# Power_Rail_Probe.net
KiCad netlist of a schematic drawn in Altium Designer
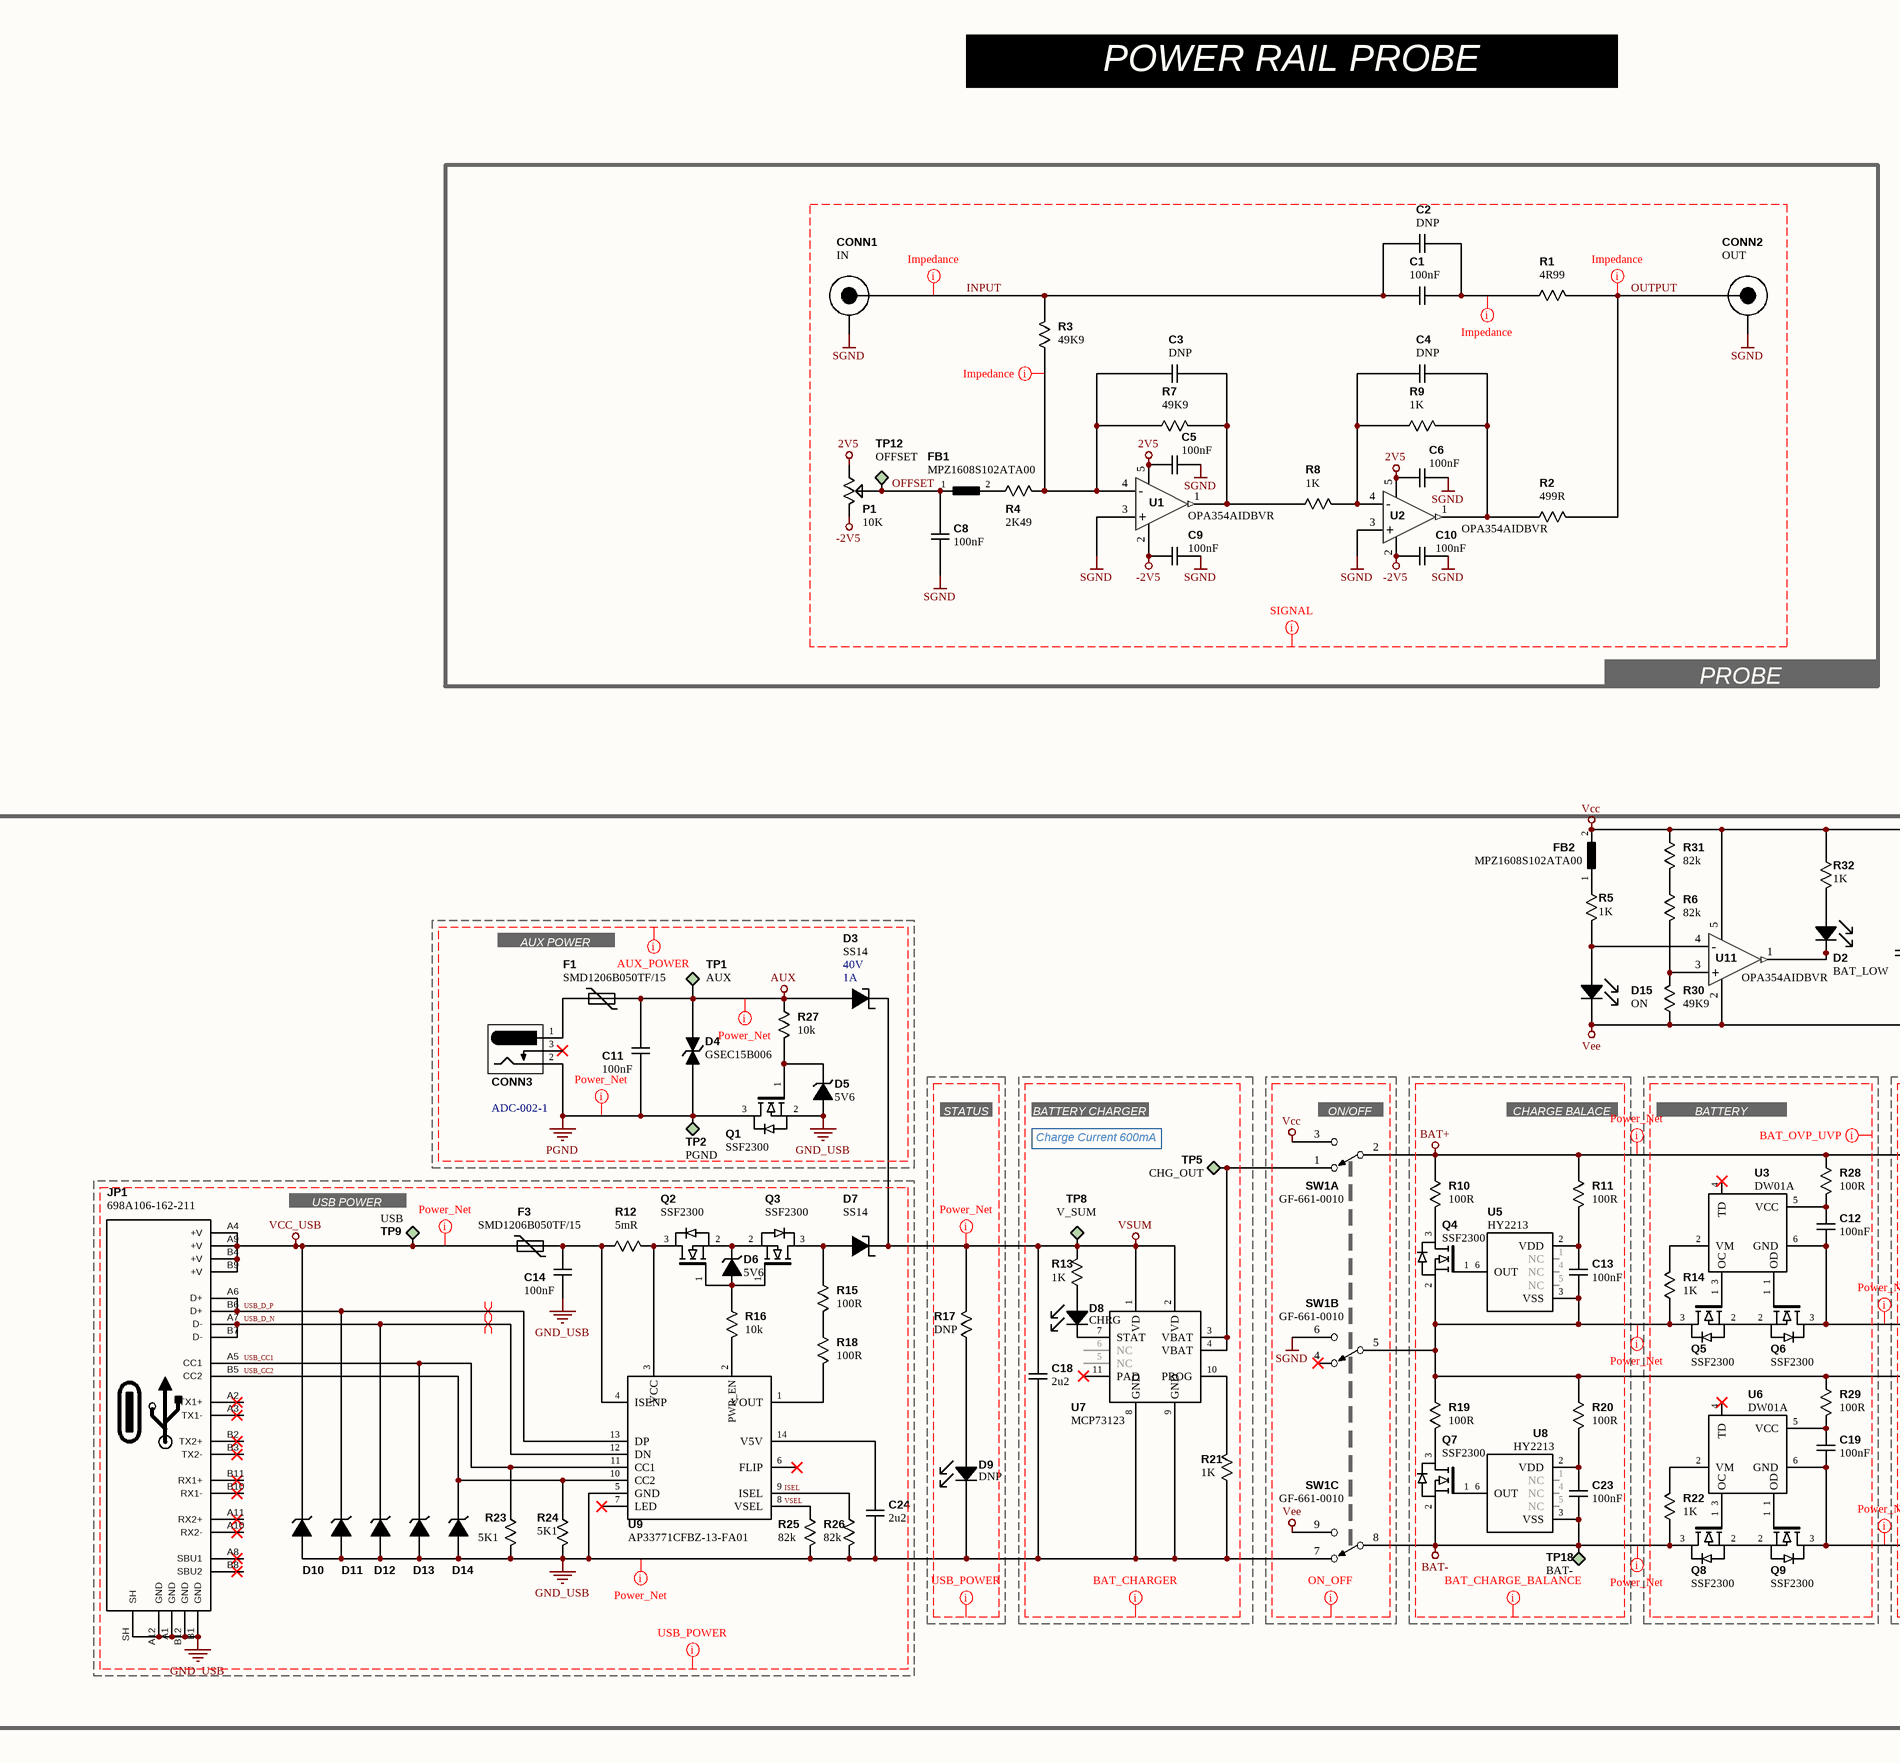
[diagram p0: Power_Rail_Probe.SchDoc, left]
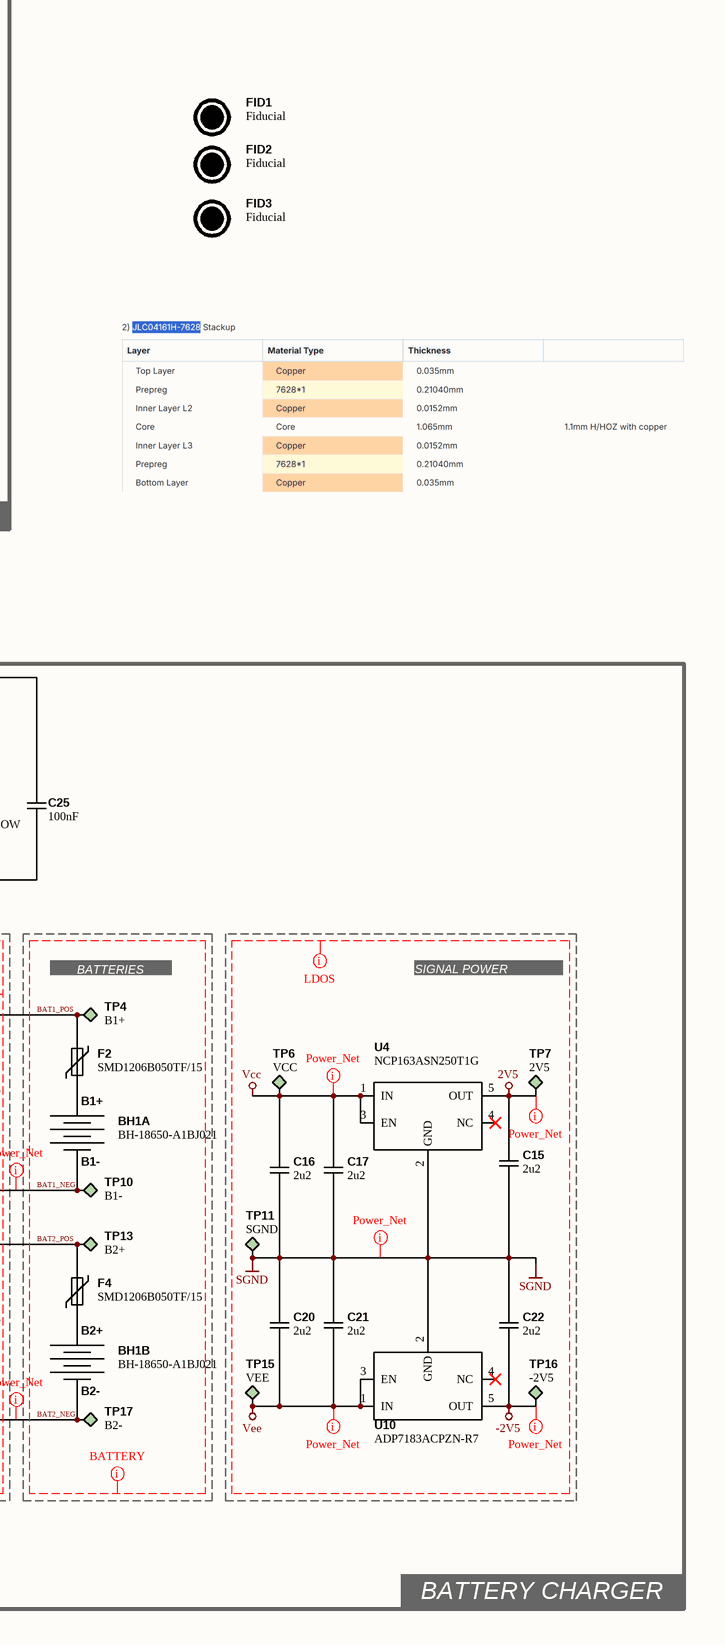
[diagram p1: Power_Rail_Probe.SchDoc, right]

(export (version "E")
  (design (tool "Eeschema 10.0.6"))
  (components
    (comp (ref "BH1")
      (value "BH-18650-A1BJ021")
      (footprint "BH-18650-A1BJ021")
      (description "2 Cell 18650 Battery Holder")
      (fields (field (name "05_DIGIKEY PART NUMBER") "Not Available"))
      (libsource (lib "Libreria_Altium") (part "BH-18650-A1BJ021"))
    )
    (comp (ref "C1")
      (value "100nF")
      (footprint "CAP_SMD_1206")
      (description "0.1 µF ±2% 50V Ceramic Capacitor C0G, NP0 1206 (3216 Metric)")
      (fields
        (field (name "04_MANUFACTURER PART NUMBER") "GRM3195C1H104GA05D")
        (field (name "05_DIGIKEY PART NUMBER") "490-GRM3195C1H104GA05DCT-ND")
      )
      (libsource (lib "Libreria_Altium") (part "Capacitor NP"))
    )
    (comp (ref "C2")
      (value "DNP")
      (footprint "CAP_SMD_0603")
      (description "0.1 µF ±10% 25V Ceramic Capacitor X7R 0603 (1608 Metric)")
      (fields
        (field (name "04_MANUFACTURER PART NUMBER") "CC0603KRX7R8BB104")
        (field (name "05_DIGIKEY PART NUMBER") "311-1341-1-ND")
      )
      (libsource (lib "Libreria_Altium") (part "Capacitor NP"))
    )
    (comp (ref "C3")
      (value "DNP")
      (footprint "CAP_SMD_0603")
      (description "0.1 µF ±10% 25V Ceramic Capacitor X7R 0603 (1608 Metric)")
      (fields
        (field (name "04_MANUFACTURER PART NUMBER") "CC0603KRX7R8BB104")
        (field (name "05_DIGIKEY PART NUMBER") "311-1341-1-ND")
      )
      (libsource (lib "Libreria_Altium") (part "Capacitor NP"))
    )
    (comp (ref "C4")
      (value "DNP")
      (footprint "CAP_SMD_0603")
      (description "0.1 µF ±10% 25V Ceramic Capacitor X7R 0603 (1608 Metric)")
      (fields
        (field (name "04_MANUFACTURER PART NUMBER") "CC0603KRX7R8BB104")
        (field (name "05_DIGIKEY PART NUMBER") "311-1341-1-ND")
      )
      (libsource (lib "Libreria_Altium") (part "Capacitor NP"))
    )
    (comp (ref "C5")
      (value "100nF")
      (footprint "CAP_SMD_0603")
      (description "0.1 µF ±10% 25V Ceramic Capacitor X7R 0603 (1608 Metric)")
      (fields
        (field (name "04_MANUFACTURER PART NUMBER") "CC0603KRX7R8BB104")
        (field (name "05_DIGIKEY PART NUMBER") "311-1341-1-ND")
      )
      (libsource (lib "Libreria_Altium") (part "Capacitor NP"))
    )
    (comp (ref "C6")
      (value "100nF")
      (footprint "CAP_SMD_0603")
      (description "0.1 µF ±10% 25V Ceramic Capacitor X7R 0603 (1608 Metric)")
      (fields
        (field (name "04_MANUFACTURER PART NUMBER") "CC0603KRX7R8BB104")
        (field (name "05_DIGIKEY PART NUMBER") "311-1341-1-ND")
      )
      (libsource (lib "Libreria_Altium") (part "Capacitor NP"))
    )
    (comp (ref "C8")
      (value "100nF")
      (footprint "CAP_SMD_0603")
      (description "0.1 µF ±10% 25V Ceramic Capacitor X7R 0603 (1608 Metric)")
      (fields
        (field (name "04_MANUFACTURER PART NUMBER") "CC0603KRX7R8BB104")
        (field (name "05_DIGIKEY PART NUMBER") "311-1341-1-ND")
      )
      (libsource (lib "Libreria_Altium") (part "Capacitor NP"))
    )
    (comp (ref "C9")
      (value "100nF")
      (footprint "CAP_SMD_0603")
      (description "0.1 µF ±10% 25V Ceramic Capacitor X7R 0603 (1608 Metric)")
      (fields
        (field (name "04_MANUFACTURER PART NUMBER") "CC0603KRX7R8BB104")
        (field (name "05_DIGIKEY PART NUMBER") "311-1341-1-ND")
      )
      (libsource (lib "Libreria_Altium") (part "Capacitor NP"))
    )
    (comp (ref "C10")
      (value "100nF")
      (footprint "CAP_SMD_0603")
      (description "0.1 µF ±10% 25V Ceramic Capacitor X7R 0603 (1608 Metric)")
      (fields
        (field (name "04_MANUFACTURER PART NUMBER") "CC0603KRX7R8BB104")
        (field (name "05_DIGIKEY PART NUMBER") "311-1341-1-ND")
      )
      (libsource (lib "Libreria_Altium") (part "Capacitor NP"))
    )
    (comp (ref "C11")
      (value "100nF")
      (footprint "CAP_SMD_0603")
      (description "0.1 µF ±10% 25V Ceramic Capacitor X7R 0603 (1608 Metric)")
      (fields
        (field (name "04_MANUFACTURER PART NUMBER") "CC0603KRX7R8BB104")
        (field (name "05_DIGIKEY PART NUMBER") "311-1341-1-ND")
      )
      (libsource (lib "Libreria_Altium") (part "Capacitor NP"))
    )
    (comp (ref "C12")
      (value "100nF")
      (footprint "CAP_SMD_0603")
      (description "0.1 µF ±10% 25V Ceramic Capacitor X7R 0603 (1608 Metric)")
      (fields
        (field (name "04_MANUFACTURER PART NUMBER") "CC0603KRX7R8BB104")
        (field (name "05_DIGIKEY PART NUMBER") "311-1341-1-ND")
      )
      (libsource (lib "Libreria_Altium") (part "Capacitor NP"))
    )
    (comp (ref "C13")
      (value "100nF")
      (footprint "CAP_SMD_0603")
      (description "0.1 µF ±10% 25V Ceramic Capacitor X7R 0603 (1608 Metric)")
      (fields
        (field (name "04_MANUFACTURER PART NUMBER") "CC0603KRX7R8BB104")
        (field (name "05_DIGIKEY PART NUMBER") "311-1341-1-ND")
      )
      (libsource (lib "Libreria_Altium") (part "Capacitor NP"))
    )
    (comp (ref "C14")
      (value "100nF")
      (footprint "CAP_SMD_0603")
      (description "0.1 µF ±10% 25V Ceramic Capacitor X7R 0603 (1608 Metric)")
      (fields
        (field (name "04_MANUFACTURER PART NUMBER") "CC0603KRX7R8BB104")
        (field (name "05_DIGIKEY PART NUMBER") "311-1341-1-ND")
      )
      (libsource (lib "Libreria_Altium") (part "Capacitor NP"))
    )
    (comp (ref "C15")
      (value "2u2")
      (footprint "CAP_SMD_0805")
      (description "2.2 µF ±10% 25V Ceramic Capacitor X7R 0805 (2012 Metric)")
      (fields
        (field (name "04_MANUFACTURER PART NUMBER") "GRM21BR71E225KE11K")
        (field (name "05_DIGIKEY PART NUMBER") "490-GRM21BR71E225KE11KCT-ND")
      )
      (libsource (lib "Libreria_Altium") (part "Capacitor NP"))
    )
    (comp (ref "C16")
      (value "2u2")
      (footprint "CAP_SMD_0805")
      (description "2.2 µF ±10% 25V Ceramic Capacitor X7R 0805 (2012 Metric)")
      (fields
        (field (name "04_MANUFACTURER PART NUMBER") "GRM21BR71E225KE11K")
        (field (name "05_DIGIKEY PART NUMBER") "490-GRM21BR71E225KE11KCT-ND")
      )
      (libsource (lib "Libreria_Altium") (part "Capacitor NP"))
    )
    (comp (ref "C17")
      (value "2u2")
      (footprint "CAP_SMD_0805")
      (description "2.2 µF ±10% 25V Ceramic Capacitor X7R 0805 (2012 Metric)")
      (fields
        (field (name "04_MANUFACTURER PART NUMBER") "GRM21BR71E225KE11K")
        (field (name "05_DIGIKEY PART NUMBER") "490-GRM21BR71E225KE11KCT-ND")
      )
      (libsource (lib "Libreria_Altium") (part "Capacitor NP"))
    )
    (comp (ref "C18")
      (value "2u2")
      (footprint "CAP_SMD_0805")
      (description "2.2 µF ±10% 25V Ceramic Capacitor X7R 0805 (2012 Metric)")
      (fields
        (field (name "04_MANUFACTURER PART NUMBER") "GRM21BR71E225KE11K")
        (field (name "05_DIGIKEY PART NUMBER") "490-GRM21BR71E225KE11KCT-ND")
      )
      (libsource (lib "Libreria_Altium") (part "Capacitor NP"))
    )
    (comp (ref "C19")
      (value "100nF")
      (footprint "CAP_SMD_0603")
      (description "0.1 µF ±10% 25V Ceramic Capacitor X7R 0603 (1608 Metric)")
      (fields
        (field (name "04_MANUFACTURER PART NUMBER") "CC0603KRX7R8BB104")
        (field (name "05_DIGIKEY PART NUMBER") "311-1341-1-ND")
      )
      (libsource (lib "Libreria_Altium") (part "Capacitor NP"))
    )
    (comp (ref "C20")
      (value "2u2")
      (footprint "CAP_SMD_0805")
      (description "2.2 µF ±10% 25V Ceramic Capacitor X7R 0805 (2012 Metric)")
      (fields
        (field (name "04_MANUFACTURER PART NUMBER") "GRM21BR71E225KE11K")
        (field (name "05_DIGIKEY PART NUMBER") "490-GRM21BR71E225KE11KCT-ND")
      )
      (libsource (lib "Libreria_Altium") (part "Capacitor NP"))
    )
    (comp (ref "C21")
      (value "2u2")
      (footprint "CAP_SMD_0805")
      (description "2.2 µF ±10% 25V Ceramic Capacitor X7R 0805 (2012 Metric)")
      (fields
        (field (name "04_MANUFACTURER PART NUMBER") "GRM21BR71E225KE11K")
        (field (name "05_DIGIKEY PART NUMBER") "490-GRM21BR71E225KE11KCT-ND")
      )
      (libsource (lib "Libreria_Altium") (part "Capacitor NP"))
    )
    (comp (ref "C22")
      (value "2u2")
      (footprint "CAP_SMD_0805")
      (description "2.2 µF ±10% 25V Ceramic Capacitor X7R 0805 (2012 Metric)")
      (fields
        (field (name "04_MANUFACTURER PART NUMBER") "GRM21BR71E225KE11K")
        (field (name "05_DIGIKEY PART NUMBER") "490-GRM21BR71E225KE11KCT-ND")
      )
      (libsource (lib "Libreria_Altium") (part "Capacitor NP"))
    )
    (comp (ref "C23")
      (value "100nF")
      (footprint "CAP_SMD_0603")
      (description "0.1 µF ±10% 25V Ceramic Capacitor X7R 0603 (1608 Metric)")
      (fields
        (field (name "04_MANUFACTURER PART NUMBER") "CC0603KRX7R8BB104")
        (field (name "05_DIGIKEY PART NUMBER") "311-1341-1-ND")
      )
      (libsource (lib "Libreria_Altium") (part "Capacitor NP"))
    )
    (comp (ref "C24")
      (value "2u2")
      (footprint "CAP_SMD_0805")
      (description "2.2 µF ±10% 25V Ceramic Capacitor X7R 0805 (2012 Metric)")
      (fields
        (field (name "04_MANUFACTURER PART NUMBER") "GRM21BR71E225KE11K")
        (field (name "05_DIGIKEY PART NUMBER") "490-GRM21BR71E225KE11KCT-ND")
      )
      (libsource (lib "Libreria_Altium") (part "Capacitor NP"))
    )
    (comp (ref "C25")
      (value "100nF")
      (footprint "CAP_SMD_0603")
      (description "0.1 µF ±10% 25V Ceramic Capacitor X7R 0603 (1608 Metric)")
      (fields
        (field (name "04_MANUFACTURER PART NUMBER") "CC0603KRX7R8BB104")
        (field (name "05_DIGIKEY PART NUMBER") "311-1341-1-ND")
      )
      (libsource (lib "Libreria_Altium") (part "Capacitor NP"))
    )
    (comp (ref "CONN1")
      (value "IN")
      (footprint "CONBNC002")
      (description "BNC Connector Jack, Female Socket 50 Ohms Panel Mount, Through Hole, Right Angle Solder")
      (fields
        (field (name "04_MANUFACTURER PART NUMBER") "CONBNC002")
        (field (name "05_DIGIKEY PART NUMBER") "343-CONBNC002-ND")
      )
      (libsource (lib "Libreria_Altium") (part "Conector BNC"))
    )
    (comp (ref "CONN2")
      (value "OUT")
      (footprint "CONBNC002")
      (description "BNC Connector Jack, Female Socket 50 Ohms Panel Mount, Through Hole, Right Angle Solder")
      (fields
        (field (name "04_MANUFACTURER PART NUMBER") "CONBNC002")
        (field (name "05_DIGIKEY PART NUMBER") "343-CONBNC002-ND")
      )
      (libsource (lib "Libreria_Altium") (part "Conector BNC"))
    )
    (comp (ref "CONN3")
      (value "AUX")
      (footprint "ADC-002A")
      (description "DC JACK")
      (fields
        (field (name "04_MANUFACTURER PART NUMBER") "ADC-002-1")
        (field (name "05_DIGIKEY PART NUMBER") "2057-ADC-002-1-ND")
      )
      (libsource (lib "Libreria_Altium") (part "DC JACK"))
    )
    (comp (ref "D2")
      (value "BAT_LOW")
      (footprint "LED_0603_1608")
      (description "Diodo LEd")
      (fields
        (field (name "04_MANUFACTURER PART NUMBER") "SML-D12U1WT86")
        (field (name "05_DIGIKEY PART NUMBER") "SML-D12U1WT86CT-ND")
      )
      (libsource (lib "Libreria_Altium") (part "Diodo LED"))
    )
    (comp (ref "D3")
      (value "SS14")
      (footprint "DO_214_AC")
      (description "Diode 40 V 1A Surface Mount DO-214AC (SMA)")
      (fields
        (field (name "04_MANUFACTURER PART NUMBER") "SS14-M3/5AT")
        (field (name "05_DIGIKEY PART NUMBER") "SS14-M3/5ATGICT-ND")
        (field (name "07_TENSIÓN") "40V")
        (field (name "08_CORRIENTE") "1A")
      )
      (libsource (lib "Libreria_Altium") (part "Diodo Schottky"))
    )
    (comp (ref "D4")
      (value "GSEC15B006")
      (footprint "SOD_323")
      (description "Diodo TVS")
      (fields (field (name "05_DIGIKEY PART NUMBER") "4786-GSEC15B006CT-ND"))
      (libsource (lib "Libreria_Altium") (part "Diodo TVS Bidireccional"))
    )
    (comp (ref "D5")
      (value "5V6")
      (footprint "SOD_323")
      (description "Diodo Zener")
      (fields
        (field (name "04_MANUFACTURER PART NUMBER") "BZT52C5V6S-7-F")
        (field (name "05_DIGIKEY PART NUMBER") "BZT52C5V6S-FDICT-ND")
      )
      (libsource (lib "Libreria_Altium") (part "Diodo Zener"))
    )
    (comp (ref "D6")
      (value "5V6")
      (footprint "SOD_323")
      (description "Diodo Zener")
      (fields
        (field (name "04_MANUFACTURER PART NUMBER") "BZT52C5V6S-7-F")
        (field (name "05_DIGIKEY PART NUMBER") "BZT52C5V6S-FDICT-ND")
      )
      (libsource (lib "Libreria_Altium") (part "Diodo Zener"))
    )
    (comp (ref "D7")
      (value "SS14")
      (footprint "DO_214_AC")
      (description "Diode 40 V 1A Surface Mount DO-214AC (SMA)")
      (fields
        (field (name "04_MANUFACTURER PART NUMBER") "SS14-M3/5AT")
        (field (name "05_DIGIKEY PART NUMBER") "SS14-M3/5ATGICT-ND")
      )
      (libsource (lib "Libreria_Altium") (part "Diodo Schottky"))
    )
    (comp (ref "D8")
      (value "CHRG")
      (footprint "LED_0603_1608")
      (description "Diodo LEd")
      (fields
        (field (name "04_MANUFACTURER PART NUMBER") "SML-D12U1WT86")
        (field (name "05_DIGIKEY PART NUMBER") "SML-D12U1WT86CT-ND")
      )
      (libsource (lib "Libreria_Altium") (part "Diodo LED"))
    )
    (comp (ref "D9")
      (value "DNP")
      (footprint "LED_0603_1608")
      (description "Diodo LEd")
      (fields
        (field (name "04_MANUFACTURER PART NUMBER") "SML-D12U1WT86")
        (field (name "05_DIGIKEY PART NUMBER") "SML-D12U1WT86CT-ND")
      )
      (libsource (lib "Libreria_Altium") (part "Diodo LED"))
    )
    (comp (ref "D10")
      (value "GSEC15B006")
      (footprint "SOD_323")
      (description "Diodo TVS")
      (fields (field (name "05_DIGIKEY PART NUMBER") "4786-GSEC15B006CT-ND"))
      (libsource (lib "Libreria_Altium") (part "Diodo TVS Unidireccional"))
    )
    (comp (ref "D11")
      (value "GSEC15B006")
      (footprint "SOD_323")
      (description "Diodo TVS")
      (fields (field (name "05_DIGIKEY PART NUMBER") "4786-GSEC15B006CT-ND"))
      (libsource (lib "Libreria_Altium") (part "Diodo TVS Unidireccional"))
    )
    (comp (ref "D12")
      (value "GSEC15B006")
      (footprint "SOD_323")
      (description "Diodo TVS")
      (fields (field (name "05_DIGIKEY PART NUMBER") "4786-GSEC15B006CT-ND"))
      (libsource (lib "Libreria_Altium") (part "Diodo TVS Unidireccional"))
    )
    (comp (ref "D13")
      (value "GSEC15B006")
      (footprint "SOD_323")
      (description "Diodo TVS")
      (fields (field (name "05_DIGIKEY PART NUMBER") "4786-GSEC15B006CT-ND"))
      (libsource (lib "Libreria_Altium") (part "Diodo TVS Unidireccional"))
    )
    (comp (ref "D14")
      (value "GSEC15B006")
      (footprint "SOD_323")
      (description "Diodo TVS")
      (fields (field (name "05_DIGIKEY PART NUMBER") "4786-GSEC15B006CT-ND"))
      (libsource (lib "Libreria_Altium") (part "Diodo TVS Unidireccional"))
    )
    (comp (ref "D15")
      (value "ON")
      (footprint "LED_0603_1608")
      (description "Diodo LEd")
      (fields
        (field (name "04_MANUFACTURER PART NUMBER") "SML-D12U1WT86")
        (field (name "05_DIGIKEY PART NUMBER") "SML-D12U1WT86CT-ND")
      )
      (libsource (lib "Libreria_Altium") (part "Diodo LED"))
    )
    (comp (ref "F1")
      (value "SMD1206B050TF/15")
      (footprint "RES_SMD_1210")
      (description "Polymeric PTC Resettable Fuse 15V 500 mA Ih Surface Mount 1206 (3216 Metric), Concave")
      (fields (field (name "05_DIGIKEY PART NUMBER") "13-SMD1206B050TF/15CT-ND"))
      (libsource (lib "") (part "Polyswitch_1"))
    )
    (comp (ref "F2")
      (value "SMD1206B050TF/15")
      (footprint "RES_SMD_1210")
      (description "Polymeric PTC Resettable Fuse 15V 500 mA Ih Surface Mount 1206 (3216 Metric), Concave")
      (fields (field (name "05_DIGIKEY PART NUMBER") "13-SMD1206B050TF/15CT-ND"))
      (libsource (lib "Libreria_Altium") (part "Polyswitch"))
    )
    (comp (ref "F3")
      (value "SMD1206B050TF/15")
      (footprint "RES_SMD_1210")
      (description "Polymeric PTC Resettable Fuse 15V 500 mA Ih Surface Mount 1206 (3216 Metric), Concave")
      (fields (field (name "05_DIGIKEY PART NUMBER") "13-SMD1206B050TF/15CT-ND"))
      (libsource (lib "") (part "Polyswitch_1"))
    )
    (comp (ref "F4")
      (value "SMD1206B050TF/15")
      (footprint "RES_SMD_1210")
      (description "Polymeric PTC Resettable Fuse 15V 500 mA Ih Surface Mount 1206 (3216 Metric), Concave")
      (fields (field (name "05_DIGIKEY PART NUMBER") "13-SMD1206B050TF/15CT-ND"))
      (libsource (lib "Libreria_Altium") (part "Polyswitch"))
    )
    (comp (ref "FB1")
      (value "MPZ1608S102ATA00")
      (footprint "FERRITE_SMD_0603")
      (description "1 kOhms @ 100 MHz 1 Power Line Ferrite Bead 0603 (1608 Metric) 800mA 300mOhm")
      (fields (field (name "05_DIGIKEY PART NUMBER") "445-MPZ1608S102ATA00CT-ND"))
      (libsource (lib "Libreria_Altium") (part "Ferrite Bead"))
    )
    (comp (ref "FB2")
      (value "MPZ1608S102ATA00")
      (footprint "FERRITE_SMD_0603")
      (description "1 kOhms @ 100 MHz 1 Power Line Ferrite Bead 0603 (1608 Metric) 800mA 300mOhm")
      (fields (field (name "05_DIGIKEY PART NUMBER") "445-MPZ1608S102ATA00CT-ND"))
      (libsource (lib "") (part "Ferrite Bead_1"))
    )
    (comp (ref "FID1")
      (value "Fiducial")
      (footprint "Fiducial")
      (description "Fiducial SMD")
      (libsource (lib "Libreria_Altium") (part "Fiducial"))
    )
    (comp (ref "FID2")
      (value "Fiducial")
      (footprint "Fiducial")
      (description "Fiducial SMD")
      (libsource (lib "Libreria_Altium") (part "Fiducial"))
    )
    (comp (ref "FID3")
      (value "Fiducial")
      (footprint "Fiducial")
      (description "Fiducial SMD")
      (libsource (lib "Libreria_Altium") (part "Fiducial"))
    )
    (comp (ref "JP1")
      (value "698A106-162-211")
      (footprint "1054500101")
      (fields
        (field (name "04_MANUFACTURER PART NUMBER") "1054500101")
        (field (name "05_DIGIKEY PART NUMBER") "WM12856CT-ND")
      )
      (libsource (lib "Libreria_Altium") (part "USB C 3.0"))
    )
    (comp (ref "P1")
      (value "10K")
      (footprint "POTENCIOMETRO_RK09K1110A0J")
      (description "10k Ohm 1 Gang Linear Through Hole Potentiometer 1.0 Turns Carbon 0.05W, 1/20W PC Pins")
      (fields
        (field (name "04_MANUFACTURER PART NUMBER") "RK09K1110A0J")
        (field (name "05_DIGIKEY PART NUMBER") "4809-RK09K1110A0J-ND")
      )
      (libsource (lib "Libreria_Altium") (part "POTENCIÓMETRO"))
    )
    (comp (ref "Q1")
      (value "SSF2300")
      (footprint "SOT_23-3")
      (description "N-Channel MOSFET SOT-23")
      (fields
        (field (name "04_MANUFACTURER PART NUMBER") "AO3414A")
        (field (name "05_DIGIKEY PART NUMBER") "4518-AO3414ACT-ND")
      )
      (libsource (lib "") (part "NMOS_1"))
    )
    (comp (ref "Q2")
      (value "SSF2300")
      (footprint "SOT_23-3")
      (description "N-Channel MOSFET SOT-23")
      (fields
        (field (name "04_MANUFACTURER PART NUMBER") "AO3414A")
        (field (name "05_DIGIKEY PART NUMBER") "4518-AO3414ACT-ND")
      )
      (libsource (lib "") (part "NMOS_2"))
    )
    (comp (ref "Q3")
      (value "SSF2300")
      (footprint "SOT_23-3")
      (description "N-Channel MOSFET SOT-23")
      (fields
        (field (name "04_MANUFACTURER PART NUMBER") "AO3414A")
        (field (name "05_DIGIKEY PART NUMBER") "4518-AO3414ACT-ND")
      )
      (libsource (lib "") (part "NMOS_3"))
    )
    (comp (ref "Q4")
      (value "SSF2300")
      (footprint "SOT_23-3")
      (description "N-Channel MOSFET SOT-23")
      (fields
        (field (name "04_MANUFACTURER PART NUMBER") "AO3414A")
        (field (name "05_DIGIKEY PART NUMBER") "4518-AO3414ACT-ND")
      )
      (libsource (lib "Libreria_Altium") (part "NMOS"))
    )
    (comp (ref "Q5")
      (value "SSF2300")
      (footprint "SOT_23-3")
      (description "N-Channel MOSFET SOT-23")
      (fields
        (field (name "04_MANUFACTURER PART NUMBER") "AO3414A")
        (field (name "05_DIGIKEY PART NUMBER") "4518-AO3414ACT-ND")
      )
      (libsource (lib "") (part "NMOS_1"))
    )
    (comp (ref "Q6")
      (value "SSF2300")
      (footprint "SOT_23-3")
      (description "N-Channel MOSFET SOT-23")
      (fields
        (field (name "04_MANUFACTURER PART NUMBER") "AO3414A")
        (field (name "05_DIGIKEY PART NUMBER") "4518-AO3414ACT-ND")
      )
      (libsource (lib "Libreria_Altium") (part "NMOS"))
    )
    (comp (ref "Q7")
      (value "SSF2300")
      (footprint "SOT_23-3")
      (description "N-Channel MOSFET SOT-23")
      (fields
        (field (name "04_MANUFACTURER PART NUMBER") "AO3414A")
        (field (name "05_DIGIKEY PART NUMBER") "4518-AO3414ACT-ND")
      )
      (libsource (lib "Libreria_Altium") (part "NMOS"))
    )
    (comp (ref "Q8")
      (value "SSF2300")
      (footprint "SOT_23-3")
      (description "N-Channel MOSFET SOT-23")
      (fields
        (field (name "04_MANUFACTURER PART NUMBER") "AO3414A")
        (field (name "05_DIGIKEY PART NUMBER") "4518-AO3414ACT-ND")
      )
      (libsource (lib "") (part "NMOS_1"))
    )
    (comp (ref "Q9")
      (value "SSF2300")
      (footprint "SOT_23-3")
      (description "N-Channel MOSFET SOT-23")
      (fields
        (field (name "04_MANUFACTURER PART NUMBER") "AO3414A")
        (field (name "05_DIGIKEY PART NUMBER") "4518-AO3414ACT-ND")
      )
      (libsource (lib "Libreria_Altium") (part "NMOS"))
    )
    (comp (ref "R1")
      (value "4R99")
      (footprint "RES_SMD_0603")
      (description "4.99 Ohms ±0.1% 0.1W, 1/10W Chip Resistor 0603 (1608 Metric) Thin Film")
      (fields
        (field (name "04_MANUFACTURER PART NUMBER") "RT0603BRD074R99L")
        (field (name "05_DIGIKEY PART NUMBER") "13-RT0603BRD074R99LCT-ND")
      )
      (libsource (lib "Libreria_Altium") (part "Resistor"))
    )
    (comp (ref "R2")
      (value "499R")
      (footprint "RES_SMD_0603")
      (description "499 Ohms ±0.1% 0.167W, 1/6W Chip Resistor 0603 (1608 Metric) Automotive AEC-Q200 Thin Film")
      (fields
        (field (name "04_MANUFACTURER PART NUMBER") "RNCF0603BTE499R")
        (field (name "05_DIGIKEY PART NUMBER") "738-RNCF0603BTE499RCT-ND")
      )
      (libsource (lib "Libreria_Altium") (part "Resistor"))
    )
    (comp (ref "R3")
      (value "49K9")
      (footprint "RES_SMD_0603")
      (description "49.9 kOhms ±0.1% 0.167W, 1/6W Chip Resistor 0603 (1608 Metric) Automotive AEC-Q200 Thin Film")
      (fields
        (field (name "04_MANUFACTURER PART NUMBER") "RNCF0603BTE49K9")
        (field (name "05_DIGIKEY PART NUMBER") "738-RNCF0603BTE49K9CT-ND")
      )
      (libsource (lib "Libreria_Altium") (part "Resistor"))
    )
    (comp (ref "R4")
      (value "2K49")
      (footprint "RES_SMD_0603")
      (description "2.49 kOhms ±0.1% 0.167W, 1/6W Chip Resistor 0603 (1608 Metric) Automotive AEC-Q200 Thin Film")
      (fields
        (field (name "04_MANUFACTURER PART NUMBER") "RNCF0603BKE2K49")
        (field (name "05_DIGIKEY PART NUMBER") "738-RNCF0603BKE2K49CT-ND")
      )
      (libsource (lib "Libreria_Altium") (part "Resistor"))
    )
    (comp (ref "R5")
      (value "1K")
      (footprint "RES_SMD_0603")
      (description "1 kOhms ±0.1% 0.167W, 1/6W Chip Resistor 0603 (1608 Metric) Automotive AEC-Q200 Thin Film")
      (fields
        (field (name "04_MANUFACTURER PART NUMBER") "RNCF0603BTE1K00")
        (field (name "05_DIGIKEY PART NUMBER") "738-RNCF0603BTE1K00CT-ND")
      )
      (libsource (lib "Libreria_Altium") (part "Resistor"))
    )
    (comp (ref "R6")
      (value "82k")
      (footprint "RES_SMD_0603")
      (description "82 kOhms ±1% 0.1W, 1/10W Chip Resistor 0603 (1608 Metric) Automotive AEC-Q200 Thick Film")
      (fields
        (field (name "04_MANUFACTURER PART NUMBER") "RMCF0603FT82K0")
        (field (name "05_DIGIKEY PART NUMBER") "RMCF0603FT82K0CT-ND")
      )
      (libsource (lib "Libreria_Altium") (part "Resistor"))
    )
    (comp (ref "R7")
      (value "49K9")
      (footprint "RES_SMD_0603")
      (description "49.9 kOhms ±0.1% 0.167W, 1/6W Chip Resistor 0603 (1608 Metric) Automotive AEC-Q200 Thin Film")
      (fields
        (field (name "04_MANUFACTURER PART NUMBER") "RNCF0603BTE49K9")
        (field (name "05_DIGIKEY PART NUMBER") "738-RNCF0603BTE49K9CT-ND")
      )
      (libsource (lib "Libreria_Altium") (part "Resistor"))
    )
    (comp (ref "R8")
      (value "1K")
      (footprint "RES_SMD_0603")
      (description "1 kOhms ±0.1% 0.167W, 1/6W Chip Resistor 0603 (1608 Metric) Automotive AEC-Q200 Thin Film")
      (fields
        (field (name "04_MANUFACTURER PART NUMBER") "RNCF0603BTE1K00")
        (field (name "05_DIGIKEY PART NUMBER") "738-RNCF0603BTE1K00CT-ND")
      )
      (libsource (lib "Libreria_Altium") (part "Resistor"))
    )
    (comp (ref "R9")
      (value "1K")
      (footprint "RES_SMD_0603")
      (description "1 kOhms ±0.1% 0.167W, 1/6W Chip Resistor 0603 (1608 Metric) Automotive AEC-Q200 Thin Film")
      (fields
        (field (name "04_MANUFACTURER PART NUMBER") "RNCF0603BTE1K00")
        (field (name "05_DIGIKEY PART NUMBER") "738-RNCF0603BTE1K00CT-ND")
      )
      (libsource (lib "Libreria_Altium") (part "Resistor"))
    )
    (comp (ref "R10")
      (value "100R")
      (footprint "RES_SMD_0603")
      (fields
        (field (name "04_MANUFACTURER PART NUMBER") "RMCF0603FT100R")
        (field (name "05_DIGIKEY PART NUMBER") "RMCF0603FT100RCT-ND")
      )
      (libsource (lib "Libreria_Altium") (part "Resistor"))
    )
    (comp (ref "R11")
      (value "100R")
      (footprint "RES_SMD_0603")
      (fields
        (field (name "04_MANUFACTURER PART NUMBER") "RMCF0603FT100R")
        (field (name "05_DIGIKEY PART NUMBER") "RMCF0603FT100RCT-ND")
      )
      (libsource (lib "Libreria_Altium") (part "Resistor"))
    )
    (comp (ref "R12")
      (value "5mR")
      (footprint "RES_SMD_0805")
      (description "5 mOhms ±1% 0.125W, 1/8W Chip Resistor 0805 (2012 Metric) Current Sense Metal Foil")
      (fields
        (field (name "04_MANUFACTURER PART NUMBER") "PE0805FRM070R005Z")
        (field (name "05_DIGIKEY PART NUMBER") "13-PE0805FRM070R005ZCT-ND")
      )
      (libsource (lib "Libreria_Altium") (part "Resistor"))
    )
    (comp (ref "R13")
      (value "1K")
      (footprint "RES_SMD_0603")
      (description "1 kOhms ±0.1% 0.167W, 1/6W Chip Resistor 0603 (1608 Metric) Automotive AEC-Q200 Thin Film")
      (fields
        (field (name "04_MANUFACTURER PART NUMBER") "RNCF0603BTE1K00")
        (field (name "05_DIGIKEY PART NUMBER") "738-RNCF0603BTE1K00CT-ND")
      )
      (libsource (lib "Libreria_Altium") (part "Resistor"))
    )
    (comp (ref "R14")
      (value "1K")
      (footprint "RES_SMD_0603")
      (description "1 kOhms ±0.1% 0.167W, 1/6W Chip Resistor 0603 (1608 Metric) Automotive AEC-Q200 Thin Film")
      (fields
        (field (name "04_MANUFACTURER PART NUMBER") "RNCF0603BTE1K00")
        (field (name "05_DIGIKEY PART NUMBER") "738-RNCF0603BTE1K00CT-ND")
      )
      (libsource (lib "Libreria_Altium") (part "Resistor"))
    )
    (comp (ref "R15")
      (value "100R")
      (footprint "RES_SMD_0603")
      (fields
        (field (name "04_MANUFACTURER PART NUMBER") "RMCF0603FT100R")
        (field (name "05_DIGIKEY PART NUMBER") "RMCF0603FT100RCT-ND")
      )
      (libsource (lib "Libreria_Altium") (part "Resistor"))
    )
    (comp (ref "R16")
      (value "10k")
      (footprint "RES_SMD_0603")
      (description "10 kOhms ±1% 0.1W, 1/10W Chip Resistor 0603 (1608 Metric) Automotive AEC-Q200 Thick Film")
      (fields
        (field (name "04_MANUFACTURER PART NUMBER") "RMCF0603FT10K0")
        (field (name "05_DIGIKEY PART NUMBER") "RMCF0603FT10K0CT-ND")
      )
      (libsource (lib "Libreria_Altium") (part "Resistor"))
    )
    (comp (ref "R17")
      (value "DNP")
      (footprint "RES_SMD_0603")
      (description "1 kOhms ±0.1% 0.167W, 1/6W Chip Resistor 0603 (1608 Metric) Automotive AEC-Q200 Thin Film")
      (fields
        (field (name "04_MANUFACTURER PART NUMBER") "RNCF0603BTE1K00")
        (field (name "05_DIGIKEY PART NUMBER") "738-RNCF0603BTE1K00CT-ND")
      )
      (libsource (lib "Libreria_Altium") (part "Resistor"))
    )
    (comp (ref "R18")
      (value "100R")
      (footprint "RES_SMD_0603")
      (fields
        (field (name "04_MANUFACTURER PART NUMBER") "RMCF0603FT100R")
        (field (name "05_DIGIKEY PART NUMBER") "RMCF0603FT100RCT-ND")
      )
      (libsource (lib "Libreria_Altium") (part "Resistor"))
    )
    (comp (ref "R19")
      (value "100R")
      (footprint "RES_SMD_0603")
      (fields
        (field (name "04_MANUFACTURER PART NUMBER") "RMCF0603FT100R")
        (field (name "05_DIGIKEY PART NUMBER") "RMCF0603FT100RCT-ND")
      )
      (libsource (lib "Libreria_Altium") (part "Resistor"))
    )
    (comp (ref "R20")
      (value "100R")
      (footprint "RES_SMD_0603")
      (fields
        (field (name "04_MANUFACTURER PART NUMBER") "RMCF0603FT100R")
        (field (name "05_DIGIKEY PART NUMBER") "RMCF0603FT100RCT-ND")
      )
      (libsource (lib "Libreria_Altium") (part "Resistor"))
    )
    (comp (ref "R21")
      (value "1K")
      (footprint "RES_SMD_0603")
      (description "1 kOhms ±0.1% 0.167W, 1/6W Chip Resistor 0603 (1608 Metric) Automotive AEC-Q200 Thin Film")
      (fields
        (field (name "04_MANUFACTURER PART NUMBER") "RNCF0603BTE1K00")
        (field (name "05_DIGIKEY PART NUMBER") "738-RNCF0603BTE1K00CT-ND")
      )
      (libsource (lib "Libreria_Altium") (part "Resistor"))
    )
    (comp (ref "R22")
      (value "1K")
      (footprint "RES_SMD_0603")
      (description "1 kOhms ±0.1% 0.167W, 1/6W Chip Resistor 0603 (1608 Metric) Automotive AEC-Q200 Thin Film")
      (fields
        (field (name "04_MANUFACTURER PART NUMBER") "RNCF0603BTE1K00")
        (field (name "05_DIGIKEY PART NUMBER") "738-RNCF0603BTE1K00CT-ND")
      )
      (libsource (lib "Libreria_Altium") (part "Resistor"))
    )
    (comp (ref "R23")
      (value "5K1")
      (footprint "RES_SMD_0603")
      (description "5.1 kOhms ±1% 0.1W, 1/10W Chip Resistor 0603 (1608 Metric) Automotive AEC-Q200 Thick Film")
      (fields
        (field (name "04_MANUFACTURER PART NUMBER") "RMCF0603FT5K10")
        (field (name "05_DIGIKEY PART NUMBER") "RMCF0603FT5K10CT-ND")
      )
      (libsource (lib "Libreria_Altium") (part "Resistor"))
    )
    (comp (ref "R24")
      (value "5K1")
      (footprint "RES_SMD_0603")
      (description "5.1 kOhms ±1% 0.1W, 1/10W Chip Resistor 0603 (1608 Metric) Automotive AEC-Q200 Thick Film")
      (fields
        (field (name "04_MANUFACTURER PART NUMBER") "RMCF0603FT5K10")
        (field (name "05_DIGIKEY PART NUMBER") "RMCF0603FT5K10CT-ND")
      )
      (libsource (lib "Libreria_Altium") (part "Resistor"))
    )
    (comp (ref "R25")
      (value "82k")
      (footprint "RES_SMD_0603")
      (description "82 kOhms ±1% 0.1W, 1/10W Chip Resistor 0603 (1608 Metric) Automotive AEC-Q200 Thick Film")
      (fields
        (field (name "04_MANUFACTURER PART NUMBER") "RMCF0603FT82K0")
        (field (name "05_DIGIKEY PART NUMBER") "RMCF0603FT82K0CT-ND")
      )
      (libsource (lib "Libreria_Altium") (part "Resistor"))
    )
    (comp (ref "R26")
      (value "82k")
      (footprint "RES_SMD_0603")
      (description "82 kOhms ±1% 0.1W, 1/10W Chip Resistor 0603 (1608 Metric) Automotive AEC-Q200 Thick Film")
      (fields
        (field (name "04_MANUFACTURER PART NUMBER") "RMCF0603FT82K0")
        (field (name "05_DIGIKEY PART NUMBER") "RMCF0603FT82K0CT-ND")
      )
      (libsource (lib "Libreria_Altium") (part "Resistor"))
    )
    (comp (ref "R27")
      (value "10k")
      (footprint "RES_SMD_0603")
      (description "10 kOhms ±1% 0.1W, 1/10W Chip Resistor 0603 (1608 Metric) Automotive AEC-Q200 Thick Film")
      (fields
        (field (name "04_MANUFACTURER PART NUMBER") "RMCF0603FT10K0")
        (field (name "05_DIGIKEY PART NUMBER") "RMCF0603FT10K0CT-ND")
      )
      (libsource (lib "Libreria_Altium") (part "Resistor"))
    )
    (comp (ref "R28")
      (value "100R")
      (footprint "RES_SMD_0603")
      (fields
        (field (name "04_MANUFACTURER PART NUMBER") "RMCF0603FT100R")
        (field (name "05_DIGIKEY PART NUMBER") "RMCF0603FT100RCT-ND")
      )
      (libsource (lib "Libreria_Altium") (part "Resistor"))
    )
    (comp (ref "R29")
      (value "100R")
      (footprint "RES_SMD_0603")
      (fields
        (field (name "04_MANUFACTURER PART NUMBER") "RMCF0603FT100R")
        (field (name "05_DIGIKEY PART NUMBER") "RMCF0603FT100RCT-ND")
      )
      (libsource (lib "Libreria_Altium") (part "Resistor"))
    )
    (comp (ref "R30")
      (value "49K9")
      (footprint "RES_SMD_0603")
      (description "49.9 kOhms ±0.1% 0.167W, 1/6W Chip Resistor 0603 (1608 Metric) Automotive AEC-Q200 Thin Film")
      (fields
        (field (name "04_MANUFACTURER PART NUMBER") "RNCF0603BTE49K9")
        (field (name "05_DIGIKEY PART NUMBER") "738-RNCF0603BTE49K9CT-ND")
      )
      (libsource (lib "Libreria_Altium") (part "Resistor"))
    )
    (comp (ref "R31")
      (value "82k")
      (footprint "RES_SMD_0603")
      (description "82 kOhms ±1% 0.1W, 1/10W Chip Resistor 0603 (1608 Metric) Automotive AEC-Q200 Thick Film")
      (fields
        (field (name "04_MANUFACTURER PART NUMBER") "RMCF0603FT82K0")
        (field (name "05_DIGIKEY PART NUMBER") "RMCF0603FT82K0CT-ND")
      )
      (libsource (lib "Libreria_Altium") (part "Resistor"))
    )
    (comp (ref "R32")
      (value "1K")
      (footprint "RES_SMD_0603")
      (description "1 kOhms ±0.1% 0.167W, 1/6W Chip Resistor 0603 (1608 Metric) Automotive AEC-Q200 Thin Film")
      (fields
        (field (name "04_MANUFACTURER PART NUMBER") "RNCF0603BTE1K00")
        (field (name "05_DIGIKEY PART NUMBER") "738-RNCF0603BTE1K00CT-ND")
      )
      (libsource (lib "Libreria_Altium") (part "Resistor"))
    )
    (comp (ref "SW1")
      (value "GF-661-0010")
      (footprint "1003P1T2B1M2QEH")
      (description "Slide Switch 3PDT Through Hole")
      (fields
        (field (name "04_MANUFACTURER PART NUMBER") "1003P1T1B1M2QEH")
        (field (name "05_DIGIKEY PART NUMBER") "EG2425-ND")
      )
      (libsource (lib "Libreria_Altium") (part "Interruptor 3PDT"))
    )
    (comp (ref "TP1")
      (value "AUX")
      (footprint "Test_Point_THT")
      (description "Testpoint")
      (fields (field (name "04_MANUFACTURER PART NUMBER") "NA"))
      (libsource (lib "Libreria_Altium") (part "TestPoint_SMD"))
    )
    (comp (ref "TP2")
      (value "PGND")
      (footprint "Test_Point_THT")
      (description "Testpoint")
      (fields (field (name "04_MANUFACTURER PART NUMBER") "NA"))
      (libsource (lib "Libreria_Altium") (part "TestPoint_SMD"))
    )
    (comp (ref "TP4")
      (value "B1+")
      (footprint "Test_Point_SMD")
      (description "Testpoint")
      (fields (field (name "04_MANUFACTURER PART NUMBER") "NA"))
      (libsource (lib "Libreria_Altium") (part "TestPoint_SMD"))
    )
    (comp (ref "TP5")
      (value "CHG_OUT")
      (footprint "Test_Point_THT")
      (description "Testpoint")
      (fields (field (name "04_MANUFACTURER PART NUMBER") "NA"))
      (libsource (lib "Libreria_Altium") (part "TestPoint_SMD"))
    )
    (comp (ref "TP6")
      (value "VCC")
      (footprint "Test_Point_THT")
      (description "Testpoint")
      (fields (field (name "04_MANUFACTURER PART NUMBER") "NA"))
      (libsource (lib "Libreria_Altium") (part "TestPoint_SMD"))
    )
    (comp (ref "TP7")
      (value "2V5")
      (footprint "Test_Point_THT")
      (description "Testpoint")
      (fields (field (name "04_MANUFACTURER PART NUMBER") "NA"))
      (libsource (lib "Libreria_Altium") (part "TestPoint_SMD"))
    )
    (comp (ref "TP8")
      (value "V_SUM")
      (footprint "Test_Point_THT")
      (description "Testpoint")
      (fields (field (name "04_MANUFACTURER PART NUMBER") "NA"))
      (libsource (lib "Libreria_Altium") (part "TestPoint_SMD"))
    )
    (comp (ref "TP9")
      (value "USB")
      (footprint "Test_Point_THT")
      (description "Testpoint")
      (fields (field (name "04_MANUFACTURER PART NUMBER") "NA"))
      (libsource (lib "Libreria_Altium") (part "TestPoint_SMD"))
    )
    (comp (ref "TP10")
      (value "B1-")
      (footprint "Test_Point_SMD")
      (description "Testpoint")
      (fields (field (name "04_MANUFACTURER PART NUMBER") "NA"))
      (libsource (lib "Libreria_Altium") (part "TestPoint_SMD"))
    )
    (comp (ref "TP11")
      (value "SGND")
      (footprint "Test_Point_THT")
      (description "Testpoint")
      (fields (field (name "04_MANUFACTURER PART NUMBER") "NA"))
      (libsource (lib "Libreria_Altium") (part "TestPoint_SMD"))
    )
    (comp (ref "TP12")
      (value "OFFSET")
      (footprint "Test_Point_THT")
      (description "Testpoint")
      (fields (field (name "04_MANUFACTURER PART NUMBER") "NA"))
      (libsource (lib "Libreria_Altium") (part "TestPoint_SMD"))
    )
    (comp (ref "TP13")
      (value "B2+")
      (footprint "Test_Point_SMD")
      (description "Testpoint")
      (fields (field (name "04_MANUFACTURER PART NUMBER") "NA"))
      (libsource (lib "Libreria_Altium") (part "TestPoint_SMD"))
    )
    (comp (ref "TP15")
      (value "VEE")
      (footprint "Test_Point_THT")
      (description "Testpoint")
      (fields (field (name "04_MANUFACTURER PART NUMBER") "NA"))
      (libsource (lib "Libreria_Altium") (part "TestPoint_SMD"))
    )
    (comp (ref "TP16")
      (value "-2V5")
      (footprint "Test_Point_THT")
      (description "Testpoint")
      (fields (field (name "04_MANUFACTURER PART NUMBER") "NA"))
      (libsource (lib "Libreria_Altium") (part "TestPoint_SMD"))
    )
    (comp (ref "TP17")
      (value "B2-")
      (footprint "Test_Point_SMD")
      (description "Testpoint")
      (fields (field (name "04_MANUFACTURER PART NUMBER") "NA"))
      (libsource (lib "Libreria_Altium") (part "TestPoint_SMD"))
    )
    (comp (ref "TP18")
      (value "BAT-")
      (footprint "Test_Point_THT")
      (description "Testpoint")
      (fields (field (name "04_MANUFACTURER PART NUMBER") "NA"))
      (libsource (lib "Libreria_Altium") (part "TestPoint_SMD"))
    )
    (comp (ref "U1")
      (value "OPA354AIDBVR")
      (footprint "SOT_23-5")
      (description "Voltage Feedback Amplifier 1 Circuit Rail-to-Rail SOT-23-5")
      (fields (field (name "05_DIGIKEY PART NUMBER") "296-26279-1-ND"))
      (libsource (lib "Libreria_Altium") (part "OPA354"))
    )
    (comp (ref "U2")
      (value "OPA354AIDBVR")
      (footprint "SOT_23-5")
      (description "Voltage Feedback Amplifier 1 Circuit Rail-to-Rail SOT-23-5")
      (fields (field (name "05_DIGIKEY PART NUMBER") "296-26279-1-ND"))
      (libsource (lib "Libreria_Altium") (part "OPA354"))
    )
    (comp (ref "U3")
      (value "DW01A")
      (footprint "SOT_23-6")
      (description "Battery Battery Protection IC Lithium Ion SOT-23-6")
      (fields
        (field (name "04_MANUFACTURER PART NUMBER") "DW01")
        (field (name "05_DIGIKEY PART NUMBER") "5399-DW01CT-ND")
      )
      (libsource (lib "Libreria_Altium") (part "DW01A"))
    )
    (comp (ref "U4")
      (value "NCP163ASN250T1G")
      (footprint "SOT_23-5")
      (description "LDO Fixed 2V5 250mA Ultra-Low Noise SOT-23-5")
      (fields (field (name "05_DIGIKEY PART NUMBER") "488-NCP163ASN250T1GCT-ND"))
      (libsource (lib "Libreria_Altium") (part "NCP163ASN250T1G"))
    )
    (comp (ref "U5")
      (value "HY2213")
      (footprint "SOT_23-6")
      (description "Balanceador de carga")
      (fields (field (name "05_DIGIKEY PART NUMBER") "NE"))
      (libsource (lib "Libreria_Altium") (part "HY2213"))
    )
    (comp (ref "U6")
      (value "DW01A")
      (footprint "SOT_23-6")
      (description "Battery Battery Protection IC Lithium Ion SOT-23-6")
      (fields
        (field (name "04_MANUFACTURER PART NUMBER") "DW01")
        (field (name "05_DIGIKEY PART NUMBER") "5399-DW01CT-ND")
      )
      (libsource (lib "Libreria_Altium") (part "DW01A"))
    )
    (comp (ref "U7")
      (value "MCP73123")
      (footprint "05_Circuitos_Integrados_SMD:DFN_10")
      (description "Battery Charger IC")
      (fields
        (field (name "04_MANUFACTURER PART NUMBER") "MCP73213T-A6SI/MF")
        (field (name "05_DIGIKEY PART NUMBER") "MCP73213T-A6SI/MFCT-ND")
      )
      (libsource (lib "Libreria_Altium") (part "MCP73123"))
    )
    (comp (ref "U8")
      (value "HY2213")
      (footprint "SOT_23-6")
      (description "Balanceador de carga")
      (fields (field (name "05_DIGIKEY PART NUMBER") "NE"))
      (libsource (lib "Libreria_Altium") (part "HY2213"))
    )
    (comp (ref "U9")
      (value "AP33771CFBZ-13-FA01")
      (footprint "DFN_14")
      (description "USB, Type-C Controller PMIC W-DFN3030-14 (Type A1)")
      (fields (field (name "05_DIGIKEY PART NUMBER") "31-AP33771CFBZ-13-FA01CT-ND"))
      (libsource (lib "Libreria_Altium") (part "AP33771C"))
    )
    (comp (ref "U10")
      (value "ADP7183ACPZN-R7")
      (footprint "SOT_23-5")
      (description "LDO Fixed -2V5 250mA Ultra-Low Noise SOT-23-5")
      (fields (field (name "05_DIGIKEY PART NUMBER") "505-ADP7183ACPZN-R7CT-ND"))
      (libsource (lib "Libreria_Altium") (part "ADP7183ACPZN-R7"))
    )
    (comp (ref "U11")
      (value "OPA354AIDBVR")
      (footprint "SOT_23-5")
      (description "Voltage Feedback Amplifier 1 Circuit Rail-to-Rail SOT-23-5")
      (fields (field (name "05_DIGIKEY PART NUMBER") "296-26279-1-ND"))
      (libsource (lib "Libreria_Altium") (part "OPA354"))
    )
  )
  (nets
    (net (code "1") (name "-2V5") (class "Default")
      (node (ref "C10") (pin "1") (pinfunction "1_1") (pintype "passive"))
      (node (ref "C22") (pin "1") (pinfunction "1_1") (pintype "passive"))
      (node (ref "C9") (pin "1") (pinfunction "1_1") (pintype "passive"))
      (node (ref "P1") (pin "1") (pinfunction "1_1") (pintype "passive"))
      (node (ref "TP16") (pin "1") (pinfunction "1_1") (pintype "passive"))
      (node (ref "U1") (pin "2") (pinfunction "GND_2") (pintype "power_in"))
      (node (ref "U10") (pin "5") (pinfunction "OUT_5") (pintype "passive"))
      (node (ref "U2") (pin "2") (pinfunction "GND_2") (pintype "power_in"))
    )
    (net (code "2") (name "/BAT1_NEG") (class "Default")
      (node (ref "BH1") (pin "N1") (pinfunction "N1_N1") (pintype "power_in"))
      (node (ref "C12") (pin "1") (pinfunction "1_1") (pintype "passive"))
      (node (ref "Q6") (pin "3") (pinfunction "D_3") (pintype "passive"))
      (node (ref "TP10") (pin "1") (pinfunction "1_1") (pintype "passive"))
      (node (ref "U3") (pin "6") (pinfunction "GND_6") (pintype "passive"))
    )
    (net (code "3") (name "/BAT2_NEG") (class "Default")
      (node (ref "BH1") (pin "N2") (pinfunction "B2-_N2") (pintype "power_in"))
      (node (ref "C19") (pin "1") (pinfunction "1_1") (pintype "passive"))
      (node (ref "Q9") (pin "3") (pinfunction "D_3") (pintype "passive"))
      (node (ref "TP17") (pin "1") (pinfunction "1_1") (pintype "passive"))
      (node (ref "U6") (pin "6") (pinfunction "GND_6") (pintype "passive"))
    )
    (net (code "4") (name "/BAT2_POS") (class "Default")
      (node (ref "C13") (pin "1") (pinfunction "1_1") (pintype "passive"))
      (node (ref "F4") (pin "2") (pinfunction "2_2") (pintype "passive"))
      (node (ref "Q4") (pin "2") (pinfunction "S_2") (pintype "passive"))
      (node (ref "Q5") (pin "3") (pinfunction "D_3") (pintype "passive"))
      (node (ref "R14") (pin "1") (pinfunction "1_1") (pintype "passive"))
      (node (ref "R19") (pin "2") (pinfunction "2_2") (pintype "passive"))
      (node (ref "R20") (pin "2") (pinfunction "2_2") (pintype "passive"))
      (node (ref "R29") (pin "2") (pinfunction "2_2") (pintype "passive"))
      (node (ref "SW1") (pin "5") (pinfunction "COM2_5") (pintype "passive"))
      (node (ref "TP13") (pin "1") (pinfunction "1_1") (pintype "passive"))
      (node (ref "U5") (pin "3") (pinfunction "VSS_3") (pintype "passive"))
    )
    (net (code "5") (name "/INPUT") (class "Default")
      (node (ref "C1") (pin "1") (pinfunction "1_1") (pintype "passive"))
      (node (ref "C2") (pin "2") (pinfunction "2_2") (pintype "passive"))
      (node (ref "CONN1") (pin "1") (pinfunction "SIGNAL_1") (pintype "passive"))
      (node (ref "R3") (pin "2") (pinfunction "2_2") (pintype "passive"))
    )
    (net (code "7") (name "/OFFSET") (class "Default")
      (node (ref "C8") (pin "2") (pinfunction "2_2") (pintype "passive"))
      (node (ref "FB1") (pin "1") (pinfunction "1_1") (pintype "passive"))
      (node (ref "P1") (pin "2") (pinfunction "2_2") (pintype "passive"))
      (node (ref "TP12") (pin "1") (pinfunction "1_1") (pintype "passive"))
    )
    (net (code "8") (name "/OUTPUT") (class "Default")
      (node (ref "CONN2") (pin "1") (pinfunction "SIGNAL_1") (pintype "passive"))
      (node (ref "R1") (pin "2") (pinfunction "2_2") (pintype "passive"))
      (node (ref "R2") (pin "2") (pinfunction "2_2") (pintype "passive"))
    )
    (net (code "9") (name "/USB_CC1") (class "Default")
      (node (ref "D13") (pin "K") (pinfunction "K_K") (pintype "passive"))
      (node (ref "JP1") (pin "A5") (pinfunction "CC1_A5") (pintype "passive"))
      (node (ref "R23") (pin "2") (pinfunction "2_2") (pintype "passive"))
      (node (ref "U9") (pin "11") (pinfunction "CC1_11") (pintype "passive"))
    )
    (net (code "10") (name "/USB_CC2") (class "Default")
      (node (ref "D14") (pin "K") (pinfunction "K_K") (pintype "passive"))
      (node (ref "JP1") (pin "B5") (pinfunction "CC2_B5") (pintype "passive"))
      (node (ref "R24") (pin "2") (pinfunction "2_2") (pintype "passive"))
      (node (ref "U9") (pin "10") (pinfunction "CC2_10") (pintype "passive"))
    )
    (net (code "11") (name "/USB_D_N") (class "Default")
      (node (ref "D12") (pin "K") (pinfunction "K_K") (pintype "passive"))
      (node (ref "JP1") (pin "A7") (pinfunction "D-_A7") (pintype "passive"))
      (node (ref "JP1") (pin "B7") (pinfunction "D-_B7") (pintype "passive"))
      (node (ref "U9") (pin "12") (pinfunction "DN_12") (pintype "passive"))
    )
    (net (code "12") (name "/USB_D_P") (class "Default")
      (node (ref "D11") (pin "K") (pinfunction "K_K") (pintype "passive"))
      (node (ref "JP1") (pin "A6") (pinfunction "D+_A6") (pintype "passive"))
      (node (ref "JP1") (pin "B6") (pinfunction "D+_B6") (pintype "passive"))
      (node (ref "U9") (pin "13") (pinfunction "DP_13") (pintype "passive"))
    )
    (net (code "14") (name "2V5") (class "Default")
      (node (ref "C15") (pin "2") (pinfunction "2_2") (pintype "passive"))
      (node (ref "C5") (pin "1") (pinfunction "1_1") (pintype "passive"))
      (node (ref "C6") (pin "1") (pinfunction "1_1") (pintype "passive"))
      (node (ref "P1") (pin "3") (pinfunction "3_3") (pintype "passive"))
      (node (ref "TP7") (pin "1") (pinfunction "1_1") (pintype "passive"))
      (node (ref "U1") (pin "5") (pinfunction "VCC_5") (pintype "power_in"))
      (node (ref "U2") (pin "5") (pinfunction "VCC_5") (pintype "power_in"))
      (node (ref "U4") (pin "5") (pinfunction "OUT_5") (pintype "passive"))
    )
    (net (code "15") (name "AUX") (class "Default")
      (node (ref "C11") (pin "2") (pinfunction "2_2") (pintype "passive"))
      (node (ref "D3") (pin "A") (pinfunction "A_A") (pintype "passive"))
      (node (ref "D4") (pin "K") (pinfunction "K_K") (pintype "passive"))
      (node (ref "F1") (pin "1") (pinfunction "1_1") (pintype "passive"))
      (node (ref "R27") (pin "2") (pinfunction "2_2") (pintype "passive"))
      (node (ref "TP1") (pin "1") (pinfunction "1_1") (pintype "passive"))
    )
    (net (code "16") (name "BAT+") (class "Default")
      (node (ref "F2") (pin "2") (pinfunction "2_2") (pintype "passive"))
      (node (ref "R10") (pin "2") (pinfunction "2_2") (pintype "passive"))
      (node (ref "R11") (pin "2") (pinfunction "2_2") (pintype "passive"))
      (node (ref "R28") (pin "2") (pinfunction "2_2") (pintype "passive"))
      (node (ref "SW1") (pin "2") (pinfunction "COM1_2") (pintype "passive"))
      (node (ref "TP4") (pin "1") (pinfunction "1_1") (pintype "passive"))
    )
    (net (code "17") (name "BAT-") (class "Default")
      (node (ref "C23") (pin "1") (pinfunction "1_1") (pintype "passive"))
      (node (ref "Q7") (pin "2") (pinfunction "S_2") (pintype "passive"))
      (node (ref "Q8") (pin "3") (pinfunction "D_3") (pintype "passive"))
      (node (ref "R22") (pin "1") (pinfunction "1_1") (pintype "passive"))
      (node (ref "SW1") (pin "8") (pinfunction "COM3_8") (pintype "passive"))
      (node (ref "TP18") (pin "1") (pinfunction "1_1") (pintype "passive"))
      (node (ref "U8") (pin "3") (pinfunction "VSS_3") (pintype "passive"))
    )
    (net (code "18") (name "GND_USB") (class "Default")
      (node (ref "C14") (pin "1") (pinfunction "1_1") (pintype "passive"))
      (node (ref "C18") (pin "1") (pinfunction "1_1") (pintype "passive"))
      (node (ref "C24") (pin "1") (pinfunction "1_1") (pintype "passive"))
      (node (ref "D10") (pin "A") (pinfunction "A_A") (pintype "passive"))
      (node (ref "D11") (pin "A") (pinfunction "A_A") (pintype "passive"))
      (node (ref "D12") (pin "A") (pinfunction "A_A") (pintype "passive"))
      (node (ref "D13") (pin "A") (pinfunction "A_A") (pintype "passive"))
      (node (ref "D14") (pin "A") (pinfunction "A_A") (pintype "passive"))
      (node (ref "D5") (pin "A") (pinfunction "A_A") (pintype "passive"))
      (node (ref "D9") (pin "K") (pinfunction "K_K") (pintype "passive"))
      (node (ref "JP1") (pin "A1") (pinfunction "GND_A1") (pintype "passive"))
      (node (ref "JP1") (pin "A12") (pinfunction "GND_A12") (pintype "passive"))
      (node (ref "JP1") (pin "B1") (pinfunction "GND_B1") (pintype "passive"))
      (node (ref "JP1") (pin "B12") (pinfunction "GND_B12") (pintype "passive"))
      (node (ref "JP1") (pin "SH") (pinfunction "SH_SH") (pintype "passive"))
      (node (ref "Q1") (pin "2") (pinfunction "S_2") (pintype "passive"))
      (node (ref "R21") (pin "1") (pinfunction "1_1") (pintype "passive"))
      (node (ref "R23") (pin "1") (pinfunction "1_1") (pintype "passive"))
      (node (ref "R24") (pin "1") (pinfunction "1_1") (pintype "passive"))
      (node (ref "R25") (pin "1") (pinfunction "1_1") (pintype "passive"))
      (node (ref "R26") (pin "1") (pinfunction "1_1") (pintype "passive"))
      (node (ref "SW1") (pin "7") (pinfunction "NC3_7") (pintype "passive"))
      (node (ref "U7") (pin "8") (pinfunction "GND_8") (pintype "passive"))
      (node (ref "U7") (pin "9") (pinfunction "GND_9") (pintype "passive"))
      (node (ref "U9") (pin "5") (pinfunction "GND_5") (pintype "passive"))
    )
    (net (code "19") (name "Net-(BH1A-B+)") (class "Default")
      (node (ref "BH1") (pin "P1") (pinfunction "B+_P1") (pintype "power_in"))
      (node (ref "F2") (pin "1") (pinfunction "1_1") (pintype "passive"))
    )
    (net (code "20") (name "Net-(BH1B-B2+)") (class "Default")
      (node (ref "BH1") (pin "P2") (pinfunction "B2+_P2") (pintype "power_in"))
      (node (ref "F4") (pin "1") (pinfunction "1_1") (pintype "passive"))
    )
    (net (code "21") (name "Net-(C1-Pad2)") (class "Default")
      (node (ref "C1") (pin "2") (pinfunction "2_2") (pintype "passive"))
      (node (ref "C2") (pin "1") (pinfunction "1_1") (pintype "passive"))
      (node (ref "R1") (pin "1") (pinfunction "1_1") (pintype "passive"))
    )
    (net (code "22") (name "Net-(CONN3-SIGNAL)") (class "Default")
      (node (ref "CONN3") (pin "1") (pinfunction "SIGNAL_1") (pintype "passive"))
      (node (ref "F1") (pin "2") (pinfunction "2_2") (pintype "passive"))
    )
    (net (code "23") (name "Net-(D2-PadA)") (class "Default")
      (node (ref "D2") (pin "A") (pinfunction "A_A") (pintype "passive"))
      (node (ref "R32") (pin "2") (pinfunction "2_2") (pintype "passive"))
    )
    (net (code "24") (name "Net-(D8-PadA)") (class "Default")
      (node (ref "D8") (pin "A") (pinfunction "A_A") (pintype "passive"))
      (node (ref "R13") (pin "1") (pinfunction "1_1") (pintype "passive"))
    )
    (net (code "25") (name "Net-(D9-PadA)") (class "Default")
      (node (ref "D9") (pin "A") (pinfunction "A_A") (pintype "passive"))
      (node (ref "R17") (pin "1") (pinfunction "1_1") (pintype "passive"))
    )
    (net (code "26") (name "Net-(FB1-Pad2)") (class "Default")
      (node (ref "FB1") (pin "2") (pinfunction "2_2") (pintype "passive"))
      (node (ref "R4") (pin "1") (pinfunction "1_1") (pintype "passive"))
    )
    (net (code "27") (name "Net-(FB2-Pad1)") (class "Default")
      (node (ref "FB2") (pin "1") (pinfunction "1_1") (pintype "passive"))
      (node (ref "R5") (pin "1") (pinfunction "1_1") (pintype "passive"))
    )
    (net (code "28") (name "Net-(Q1-G)") (class "Default")
      (node (ref "D5") (pin "K") (pinfunction "K_K") (pintype "passive"))
      (node (ref "Q1") (pin "1") (pinfunction "G_1") (pintype "passive"))
      (node (ref "R27") (pin "1") (pinfunction "1_1") (pintype "passive"))
    )
    (net (code "29") (name "Net-(Q2-D)") (class "Default")
      (node (ref "Q2") (pin "3") (pinfunction "D_3") (pintype "passive"))
      (node (ref "R12") (pin "1") (pinfunction "1_1") (pintype "passive"))
      (node (ref "U9") (pin "3") (pinfunction "VCC_3") (pintype "passive"))
    )
    (net (code "30") (name "Net-(Q2-G)") (class "Default")
      (node (ref "D6") (pin "A") (pinfunction "A_A") (pintype "passive"))
      (node (ref "Q2") (pin "1") (pinfunction "G_1") (pintype "passive"))
      (node (ref "Q3") (pin "1") (pinfunction "G_1") (pintype "passive"))
      (node (ref "R16") (pin "2") (pinfunction "2_2") (pintype "passive"))
    )
    (net (code "31") (name "Net-(Q2-S)") (class "Default")
      (node (ref "D6") (pin "K") (pinfunction "K_K") (pintype "passive"))
      (node (ref "Q2") (pin "2") (pinfunction "S_2") (pintype "passive"))
      (node (ref "Q3") (pin "2") (pinfunction "S_2") (pintype "passive"))
    )
    (net (code "32") (name "Net-(Q3-D)") (class "Default")
      (node (ref "D7") (pin "A") (pinfunction "A_A") (pintype "passive"))
      (node (ref "Q3") (pin "3") (pinfunction "D_3") (pintype "passive"))
      (node (ref "R15") (pin "2") (pinfunction "2_2") (pintype "passive"))
    )
    (net (code "33") (name "Net-(Q4-D)") (class "Default")
      (node (ref "Q4") (pin "3") (pinfunction "D_3") (pintype "passive"))
      (node (ref "R10") (pin "1") (pinfunction "1_1") (pintype "passive"))
    )
    (net (code "34") (name "Net-(Q4-G)") (class "Default")
      (node (ref "Q4") (pin "1") (pinfunction "G_1") (pintype "passive"))
      (node (ref "U5") (pin "6") (pinfunction "OUT_6") (pintype "passive"))
    )
    (net (code "35") (name "Net-(Q5-G)") (class "Default")
      (node (ref "Q5") (pin "1") (pinfunction "G_1") (pintype "passive"))
      (node (ref "U3") (pin "3") (pinfunction "OC_3") (pintype "passive"))
    )
    (net (code "36") (name "Net-(Q5-S)") (class "Default")
      (node (ref "Q5") (pin "2") (pinfunction "S_2") (pintype "passive"))
      (node (ref "Q6") (pin "2") (pinfunction "S_2") (pintype "passive"))
    )
    (net (code "37") (name "Net-(Q6-G)") (class "Default")
      (node (ref "Q6") (pin "1") (pinfunction "G_1") (pintype "passive"))
      (node (ref "U3") (pin "1") (pinfunction "OD_1") (pintype "passive"))
    )
    (net (code "38") (name "Net-(Q7-D)") (class "Default")
      (node (ref "Q7") (pin "3") (pinfunction "D_3") (pintype "passive"))
      (node (ref "R19") (pin "1") (pinfunction "1_1") (pintype "passive"))
    )
    (net (code "39") (name "Net-(Q7-G)") (class "Default")
      (node (ref "Q7") (pin "1") (pinfunction "G_1") (pintype "passive"))
      (node (ref "U8") (pin "6") (pinfunction "OUT_6") (pintype "passive"))
    )
    (net (code "40") (name "Net-(Q8-G)") (class "Default")
      (node (ref "Q8") (pin "1") (pinfunction "G_1") (pintype "passive"))
      (node (ref "U6") (pin "3") (pinfunction "OC_3") (pintype "passive"))
    )
    (net (code "41") (name "Net-(Q8-S)") (class "Default")
      (node (ref "Q8") (pin "2") (pinfunction "S_2") (pintype "passive"))
      (node (ref "Q9") (pin "2") (pinfunction "S_2") (pintype "passive"))
    )
    (net (code "42") (name "Net-(Q9-G)") (class "Default")
      (node (ref "Q9") (pin "1") (pinfunction "G_1") (pintype "passive"))
      (node (ref "U6") (pin "1") (pinfunction "OD_1") (pintype "passive"))
    )
    (net (code "43") (name "Net-(R15-Pad1)") (class "Default")
      (node (ref "R15") (pin "1") (pinfunction "1_1") (pintype "passive"))
      (node (ref "R18") (pin "2") (pinfunction "2_2") (pintype "passive"))
    )
    (net (code "44") (name "Net-(R31-Pad1)") (class "Default")
      (node (ref "R31") (pin "1") (pinfunction "1_1") (pintype "passive"))
      (node (ref "R6") (pin "2") (pinfunction "2_2") (pintype "passive"))
    )
    (net (code "45") (name "Net-(SW1A-NC1)") (class "Default")
      (node (ref "SW1") (pin "1") (pinfunction "NC1_1") (pintype "passive"))
      (node (ref "TP5") (pin "1") (pinfunction "1_1") (pintype "passive"))
      (node (ref "U7") (pin "3") (pinfunction "VBAT_3") (pintype "passive"))
      (node (ref "U7") (pin "4") (pinfunction "VBAT_4") (pintype "passive"))
    )
    (net (code "46") (name "Net-(U1--)") (class "Default")
      (node (ref "C3") (pin "2") (pinfunction "2_2") (pintype "passive"))
      (node (ref "R3") (pin "1") (pinfunction "1_1") (pintype "passive"))
      (node (ref "R4") (pin "2") (pinfunction "2_2") (pintype "passive"))
      (node (ref "R7") (pin "1") (pinfunction "1_1") (pintype "passive"))
      (node (ref "U1") (pin "4") (pinfunction "-_4") (pintype "tri_state"))
    )
    (net (code "47") (name "Net-(U1-OUT)") (class "Default")
      (node (ref "C3") (pin "1") (pinfunction "1_1") (pintype "passive"))
      (node (ref "R7") (pin "2") (pinfunction "2_2") (pintype "passive"))
      (node (ref "R8") (pin "1") (pinfunction "1_1") (pintype "passive"))
      (node (ref "U1") (pin "1") (pinfunction "OUT_1") (pintype "output"))
    )
    (net (code "48") (name "Net-(U2--)") (class "Default")
      (node (ref "C4") (pin "2") (pinfunction "2_2") (pintype "passive"))
      (node (ref "R8") (pin "2") (pinfunction "2_2") (pintype "passive"))
      (node (ref "R9") (pin "1") (pinfunction "1_1") (pintype "passive"))
      (node (ref "U2") (pin "4") (pinfunction "-_4") (pintype "tri_state"))
    )
    (net (code "49") (name "Net-(U2-OUT)") (class "Default")
      (node (ref "C4") (pin "1") (pinfunction "1_1") (pintype "passive"))
      (node (ref "R2") (pin "1") (pinfunction "1_1") (pintype "passive"))
      (node (ref "R9") (pin "2") (pinfunction "2_2") (pintype "passive"))
      (node (ref "U2") (pin "1") (pinfunction "OUT_1") (pintype "output"))
    )
    (net (code "50") (name "Net-(U3-VCC)") (class "Default")
      (node (ref "C12") (pin "2") (pinfunction "2_2") (pintype "passive"))
      (node (ref "R28") (pin "1") (pinfunction "1_1") (pintype "passive"))
      (node (ref "U3") (pin "5") (pinfunction "VCC_5") (pintype "passive"))
    )
    (net (code "51") (name "Net-(U3-VM)") (class "Default")
      (node (ref "R14") (pin "2") (pinfunction "2_2") (pintype "passive"))
      (node (ref "U3") (pin "2") (pinfunction "VM_2") (pintype "passive"))
    )
    (net (code "52") (name "Net-(U5-VDD)") (class "Default")
      (node (ref "C13") (pin "2") (pinfunction "2_2") (pintype "passive"))
      (node (ref "R11") (pin "1") (pinfunction "1_1") (pintype "passive"))
      (node (ref "U5") (pin "2") (pinfunction "VDD_2") (pintype "passive"))
    )
    (net (code "53") (name "Net-(U6-VCC)") (class "Default")
      (node (ref "C19") (pin "2") (pinfunction "2_2") (pintype "passive"))
      (node (ref "R29") (pin "1") (pinfunction "1_1") (pintype "passive"))
      (node (ref "U6") (pin "5") (pinfunction "VCC_5") (pintype "passive"))
    )
    (net (code "54") (name "Net-(U6-VM)") (class "Default")
      (node (ref "R22") (pin "2") (pinfunction "2_2") (pintype "passive"))
      (node (ref "U6") (pin "2") (pinfunction "VM_2") (pintype "passive"))
    )
    (net (code "55") (name "Net-(U7-PROG)") (class "Default")
      (node (ref "R21") (pin "2") (pinfunction "2_2") (pintype "passive"))
      (node (ref "U7") (pin "10") (pinfunction "PROG_10") (pintype "passive"))
    )
    (net (code "56") (name "Net-(U7-STAT)") (class "Default")
      (node (ref "D8") (pin "K") (pinfunction "K_K") (pintype "passive"))
      (node (ref "U7") (pin "7") (pinfunction "STAT_7") (pintype "passive"))
    )
    (net (code "57") (name "Net-(U8-VDD)") (class "Default")
      (node (ref "C23") (pin "2") (pinfunction "2_2") (pintype "passive"))
      (node (ref "R20") (pin "1") (pinfunction "1_1") (pintype "passive"))
      (node (ref "U8") (pin "2") (pinfunction "VDD_2") (pintype "passive"))
    )
    (net (code "58") (name "Net-(U9-ISEL)") (class "Default")
      (node (ref "R26") (pin "2") (pinfunction "2_2") (pintype "passive"))
      (node (ref "U9") (pin "9") (pinfunction "ISEL_9") (pintype "passive"))
    )
    (net (code "59") (name "Net-(U9-ISENP)") (class "Default")
      (node (ref "C14") (pin "2") (pinfunction "2_2") (pintype "passive"))
      (node (ref "F3") (pin "1") (pinfunction "1_1") (pintype "passive"))
      (node (ref "R12") (pin "2") (pinfunction "2_2") (pintype "passive"))
      (node (ref "U9") (pin "4") (pinfunction "ISENP_4") (pintype "passive"))
    )
    (net (code "60") (name "Net-(U9-PWR_EN)") (class "Default")
      (node (ref "R16") (pin "1") (pinfunction "1_1") (pintype "passive"))
      (node (ref "U9") (pin "2") (pinfunction "PWR_EN_2") (pintype "passive"))
    )
    (net (code "61") (name "Net-(U9-V5V)") (class "Default")
      (node (ref "C24") (pin "2") (pinfunction "2_2") (pintype "passive"))
      (node (ref "U9") (pin "14") (pinfunction "V5V_14") (pintype "passive"))
    )
    (net (code "62") (name "Net-(U9-VOUT)") (class "Default")
      (node (ref "R18") (pin "1") (pinfunction "1_1") (pintype "passive"))
      (node (ref "U9") (pin "1") (pinfunction "VOUT_1") (pintype "passive"))
    )
    (net (code "63") (name "Net-(U9-VSEL)") (class "Default")
      (node (ref "R25") (pin "2") (pinfunction "2_2") (pintype "passive"))
      (node (ref "U9") (pin "8") (pinfunction "VSEL_8") (pintype "passive"))
    )
    (net (code "64") (name "Net-(U11-+)") (class "Default")
      (node (ref "R30") (pin "2") (pinfunction "2_2") (pintype "passive"))
      (node (ref "R6") (pin "1") (pinfunction "1_1") (pintype "passive"))
      (node (ref "U11") (pin "3") (pinfunction "+_3") (pintype "tri_state"))
    )
    (net (code "65") (name "Net-(U11--)") (class "Default")
      (node (ref "D15") (pin "A") (pinfunction "A_A") (pintype "passive"))
      (node (ref "R5") (pin "2") (pinfunction "2_2") (pintype "passive"))
      (node (ref "U11") (pin "4") (pinfunction "-_4") (pintype "tri_state"))
    )
    (net (code "66") (name "Net-(U11-OUT)") (class "Default")
      (node (ref "D2") (pin "K") (pinfunction "K_K") (pintype "passive"))
      (node (ref "U11") (pin "1") (pinfunction "OUT_1") (pintype "output"))
    )
    (net (code "67") (name "PGND") (class "Default")
      (node (ref "C11") (pin "1") (pinfunction "1_1") (pintype "passive"))
      (node (ref "CONN3") (pin "2") (pinfunction "2_2") (pintype "passive"))
      (node (ref "D4") (pin "A") (pinfunction "A_A") (pintype "passive"))
      (node (ref "Q1") (pin "3") (pinfunction "D_3") (pintype "passive"))
      (node (ref "TP2") (pin "1") (pinfunction "1_1") (pintype "passive"))
    )
    (net (code "68") (name "SGND") (class "Default")
      (node (ref "C10") (pin "2") (pinfunction "2_2") (pintype "passive"))
      (node (ref "C15") (pin "1") (pinfunction "1_1") (pintype "passive"))
      (node (ref "C16") (pin "1") (pinfunction "1_1") (pintype "passive"))
      (node (ref "C17") (pin "1") (pinfunction "1_1") (pintype "passive"))
      (node (ref "C20") (pin "2") (pinfunction "2_2") (pintype "passive"))
      (node (ref "C21") (pin "2") (pinfunction "2_2") (pintype "passive"))
      (node (ref "C22") (pin "2") (pinfunction "2_2") (pintype "passive"))
      (node (ref "C5") (pin "2") (pinfunction "2_2") (pintype "passive"))
      (node (ref "C6") (pin "2") (pinfunction "2_2") (pintype "passive"))
      (node (ref "C8") (pin "1") (pinfunction "1_1") (pintype "passive"))
      (node (ref "C9") (pin "2") (pinfunction "2_2") (pintype "passive"))
      (node (ref "CONN1") (pin "2") (pinfunction "2_2") (pintype "passive"))
      (node (ref "CONN2") (pin "2") (pinfunction "2_2") (pintype "passive"))
      (node (ref "SW1") (pin "6") (pinfunction "NO2_6") (pintype "passive"))
      (node (ref "TP11") (pin "1") (pinfunction "1_1") (pintype "passive"))
      (node (ref "U1") (pin "3") (pinfunction "+_3") (pintype "tri_state"))
      (node (ref "U10") (pin "2") (pinfunction "GND_2") (pintype "passive"))
      (node (ref "U2") (pin "3") (pinfunction "+_3") (pintype "tri_state"))
      (node (ref "U4") (pin "2") (pinfunction "GND_2") (pintype "passive"))
    )
    (net (code "69") (name "VCC_USB") (class "Default")
      (node (ref "D10") (pin "K") (pinfunction "K_K") (pintype "passive"))
      (node (ref "F3") (pin "2") (pinfunction "2_2") (pintype "passive"))
      (node (ref "JP1") (pin "A4") (pinfunction "+V_A4") (pintype "passive"))
      (node (ref "JP1") (pin "A9") (pinfunction "+V_A9") (pintype "passive"))
      (node (ref "JP1") (pin "B4") (pinfunction "+V_B4") (pintype "passive"))
      (node (ref "JP1") (pin "B9") (pinfunction "+V_B9") (pintype "passive"))
      (node (ref "TP9") (pin "1") (pinfunction "1_1") (pintype "passive"))
    )
    (net (code "70") (name "VSUM") (class "Default")
      (node (ref "C18") (pin "2") (pinfunction "2_2") (pintype "passive"))
      (node (ref "D3") (pin "K") (pinfunction "K_K") (pintype "passive"))
      (node (ref "D7") (pin "K") (pinfunction "K_K") (pintype "passive"))
      (node (ref "R13") (pin "2") (pinfunction "2_2") (pintype "passive"))
      (node (ref "R17") (pin "2") (pinfunction "2_2") (pintype "passive"))
      (node (ref "TP8") (pin "1") (pinfunction "1_1") (pintype "passive"))
      (node (ref "U7") (pin "1") (pinfunction "VD_1") (pintype "passive"))
      (node (ref "U7") (pin "2") (pinfunction "VD_2") (pintype "passive"))
    )
    (net (code "71") (name "Vcc") (class "Default")
      (node (ref "C16") (pin "2") (pinfunction "2_2") (pintype "passive"))
      (node (ref "C17") (pin "2") (pinfunction "2_2") (pintype "passive"))
      (node (ref "C25") (pin "1") (pinfunction "1_1") (pintype "passive"))
      (node (ref "FB2") (pin "2") (pinfunction "2_2") (pintype "passive"))
      (node (ref "R31") (pin "2") (pinfunction "2_2") (pintype "passive"))
      (node (ref "R32") (pin "1") (pinfunction "1_1") (pintype "passive"))
      (node (ref "SW1") (pin "3") (pinfunction "NO1_3") (pintype "passive"))
      (node (ref "TP6") (pin "1") (pinfunction "1_1") (pintype "passive"))
      (node (ref "U11") (pin "5") (pinfunction "VCC_5") (pintype "power_in"))
      (node (ref "U4") (pin "1") (pinfunction "IN_1") (pintype "passive"))
      (node (ref "U4") (pin "3") (pinfunction "EN_3") (pintype "passive"))
    )
    (net (code "72") (name "Vee") (class "Default")
      (node (ref "C20") (pin "1") (pinfunction "1_1") (pintype "passive"))
      (node (ref "C21") (pin "1") (pinfunction "1_1") (pintype "passive"))
      (node (ref "C25") (pin "2") (pinfunction "2_2") (pintype "passive"))
      (node (ref "D15") (pin "K") (pinfunction "K_K") (pintype "passive"))
      (node (ref "R30") (pin "1") (pinfunction "1_1") (pintype "passive"))
      (node (ref "SW1") (pin "9") (pinfunction "NO3_9") (pintype "passive"))
      (node (ref "TP15") (pin "1") (pinfunction "1_1") (pintype "passive"))
      (node (ref "U10") (pin "1") (pinfunction "IN_1") (pintype "passive"))
      (node (ref "U10") (pin "3") (pinfunction "EN_3") (pintype "passive"))
      (node (ref "U11") (pin "2") (pinfunction "GND_2") (pintype "power_in"))
    )
    (net (code "73") (name "unconnected-(CONN3-Pad3)") (class "Default")
      (node (ref "CONN3") (pin "3") (pinfunction "3_3") (pintype "passive+no_connect"))
    )
    (net (code "74") (name "unconnected-(FID1-Pad5)") (class "Default")
      (node (ref "FID1") (pin "5") (pinfunction "5_5") (pintype "passive"))
    )
    (net (code "75") (name "unconnected-(FID2-Pad5)") (class "Default")
      (node (ref "FID2") (pin "5") (pinfunction "5_5") (pintype "passive"))
    )
    (net (code "76") (name "unconnected-(FID3-Pad5)") (class "Default")
      (node (ref "FID3") (pin "5") (pinfunction "5_5") (pintype "passive"))
    )
    (net (code "77") (name "unconnected-(JP1-RX1+-PadB11)") (class "Default")
      (node (ref "JP1") (pin "B11") (pinfunction "RX1+_B11") (pintype "passive+no_connect"))
    )
    (net (code "78") (name "unconnected-(JP1-RX1--PadB10)") (class "Default")
      (node (ref "JP1") (pin "B10") (pinfunction "RX1-_B10") (pintype "passive+no_connect"))
    )
    (net (code "79") (name "unconnected-(JP1-RX2+-PadA11)") (class "Default")
      (node (ref "JP1") (pin "A11") (pinfunction "RX2+_A11") (pintype "passive+no_connect"))
    )
    (net (code "80") (name "unconnected-(JP1-RX2--PadA10)") (class "Default")
      (node (ref "JP1") (pin "A10") (pinfunction "RX2-_A10") (pintype "passive+no_connect"))
    )
    (net (code "81") (name "unconnected-(JP1-SBU1-PadA8)") (class "Default")
      (node (ref "JP1") (pin "A8") (pinfunction "SBU1_A8") (pintype "passive+no_connect"))
    )
    (net (code "82") (name "unconnected-(JP1-SBU2-PadB8)") (class "Default")
      (node (ref "JP1") (pin "B8") (pinfunction "SBU2_B8") (pintype "passive+no_connect"))
    )
    (net (code "83") (name "unconnected-(JP1-TX1+-PadA2)") (class "Default")
      (node (ref "JP1") (pin "A2") (pinfunction "TX1+_A2") (pintype "passive+no_connect"))
    )
    (net (code "84") (name "unconnected-(JP1-TX1--PadA3)") (class "Default")
      (node (ref "JP1") (pin "A3") (pinfunction "TX1-_A3") (pintype "passive+no_connect"))
    )
    (net (code "85") (name "unconnected-(JP1-TX2+-PadB2)") (class "Default")
      (node (ref "JP1") (pin "B2") (pinfunction "TX2+_B2") (pintype "passive+no_connect"))
    )
    (net (code "86") (name "unconnected-(JP1-TX2--PadB3)") (class "Default")
      (node (ref "JP1") (pin "B3") (pinfunction "TX2-_B3") (pintype "passive+no_connect"))
    )
    (net (code "87") (name "unconnected-(SW1B-NC2-Pad4)") (class "Default")
      (node (ref "SW1") (pin "4") (pinfunction "NC2_4") (pintype "passive+no_connect"))
    )
    (net (code "88") (name "unconnected-(U3-TD-Pad4)") (class "Default")
      (node (ref "U3") (pin "4") (pinfunction "TD_4") (pintype "passive+no_connect"))
    )
    (net (code "89") (name "unconnected-(U4-NC-Pad4)") (class "Default")
      (node (ref "U4") (pin "4") (pinfunction "NC_4") (pintype "passive+no_connect"))
    )
    (net (code "90") (name "unconnected-(U5-NC-Pad1)") (class "Default")
      (node (ref "U5") (pin "1") (pinfunction "NC_1") (pintype "passive"))
    )
    (net (code "91") (name "unconnected-(U5-NC-Pad4)") (class "Default")
      (node (ref "U5") (pin "4") (pinfunction "NC_4") (pintype "passive"))
    )
    (net (code "92") (name "unconnected-(U5-NC-Pad5)") (class "Default")
      (node (ref "U5") (pin "5") (pinfunction "NC_5") (pintype "passive"))
    )
    (net (code "93") (name "unconnected-(U6-TD-Pad4)") (class "Default")
      (node (ref "U6") (pin "4") (pinfunction "TD_4") (pintype "passive+no_connect"))
    )
    (net (code "94") (name "unconnected-(U7-NC-Pad5)") (class "Default")
      (node (ref "U7") (pin "5") (pinfunction "NC_5") (pintype "passive"))
    )
    (net (code "95") (name "unconnected-(U7-NC-Pad6)") (class "Default")
      (node (ref "U7") (pin "6") (pinfunction "NC_6") (pintype "passive"))
    )
    (net (code "96") (name "unconnected-(U7-PAD-Pad11)") (class "Default")
      (node (ref "U7") (pin "11") (pinfunction "PAD_11") (pintype "passive+no_connect"))
    )
    (net (code "97") (name "unconnected-(U8-NC-Pad1)") (class "Default")
      (node (ref "U8") (pin "1") (pinfunction "NC_1") (pintype "passive"))
    )
    (net (code "98") (name "unconnected-(U8-NC-Pad4)") (class "Default")
      (node (ref "U8") (pin "4") (pinfunction "NC_4") (pintype "passive"))
    )
    (net (code "99") (name "unconnected-(U8-NC-Pad5)") (class "Default")
      (node (ref "U8") (pin "5") (pinfunction "NC_5") (pintype "passive"))
    )
    (net (code "100") (name "unconnected-(U9-FLIP-Pad6)") (class "Default")
      (node (ref "U9") (pin "6") (pinfunction "FLIP_6") (pintype "passive+no_connect"))
    )
    (net (code "101") (name "unconnected-(U9-LED-Pad7)") (class "Default")
      (node (ref "U9") (pin "7") (pinfunction "LED_7") (pintype "passive+no_connect"))
    )
    (net (code "102") (name "unconnected-(U10-NC-Pad4)") (class "Default")
      (node (ref "U10") (pin "4") (pinfunction "NC_4") (pintype "passive+no_connect"))
    )
  )
)
